# sunbeam2.net
KiCad netlist of a schematic drawn in EAGLE
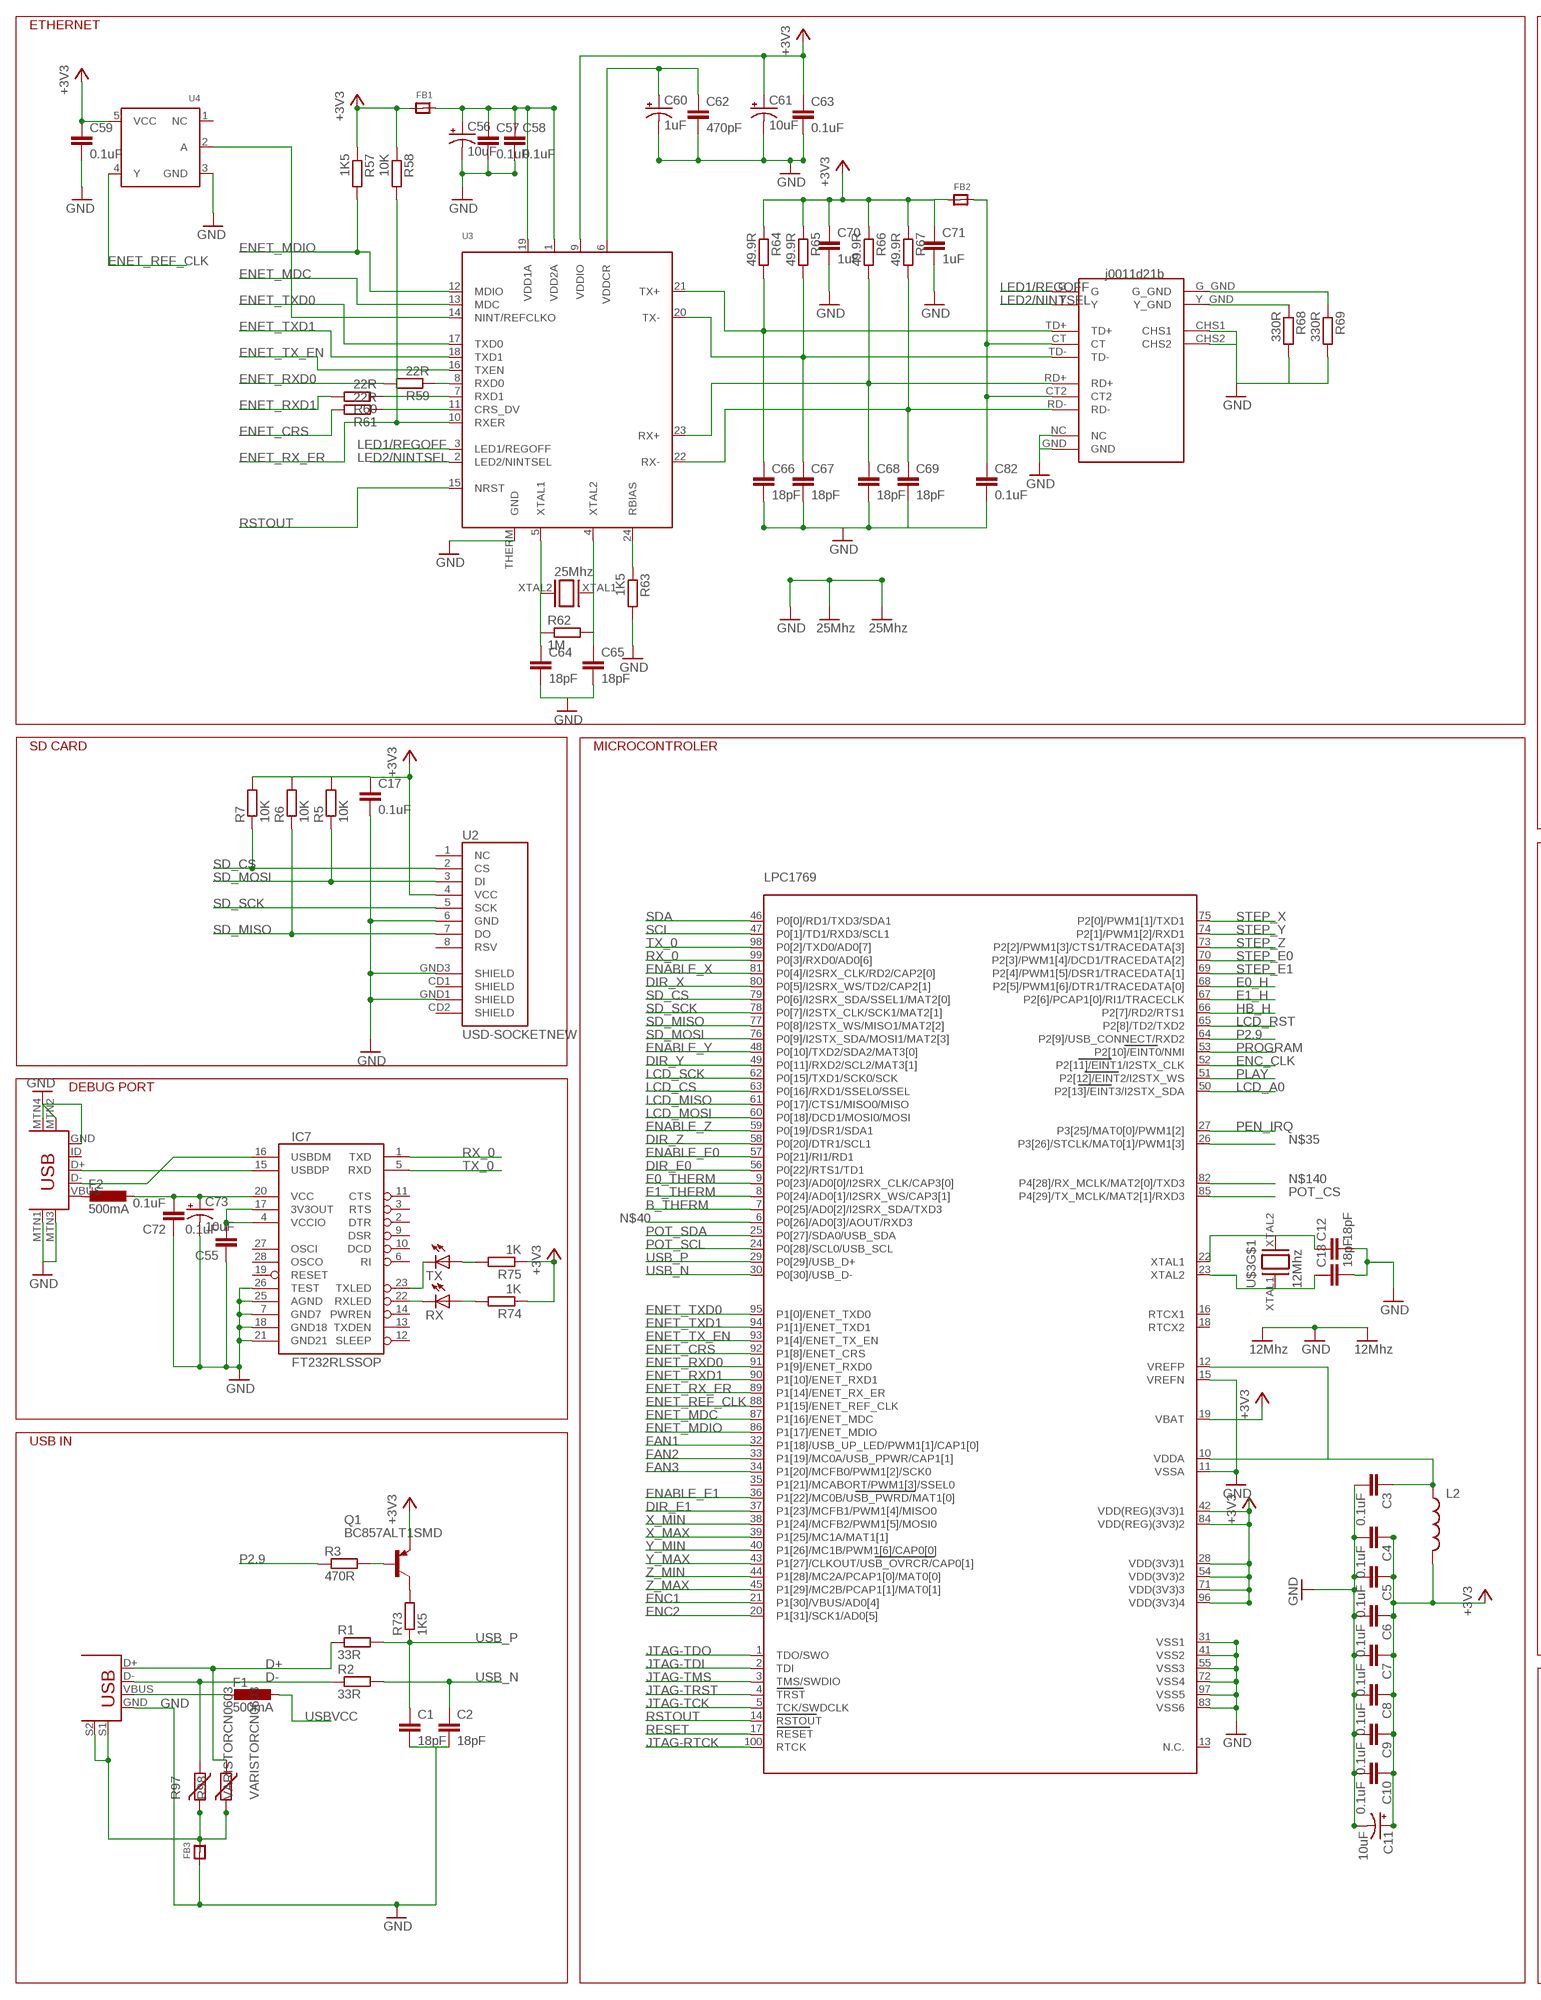
[diagram p0: schematic, sheet 1, part 1 of 2]
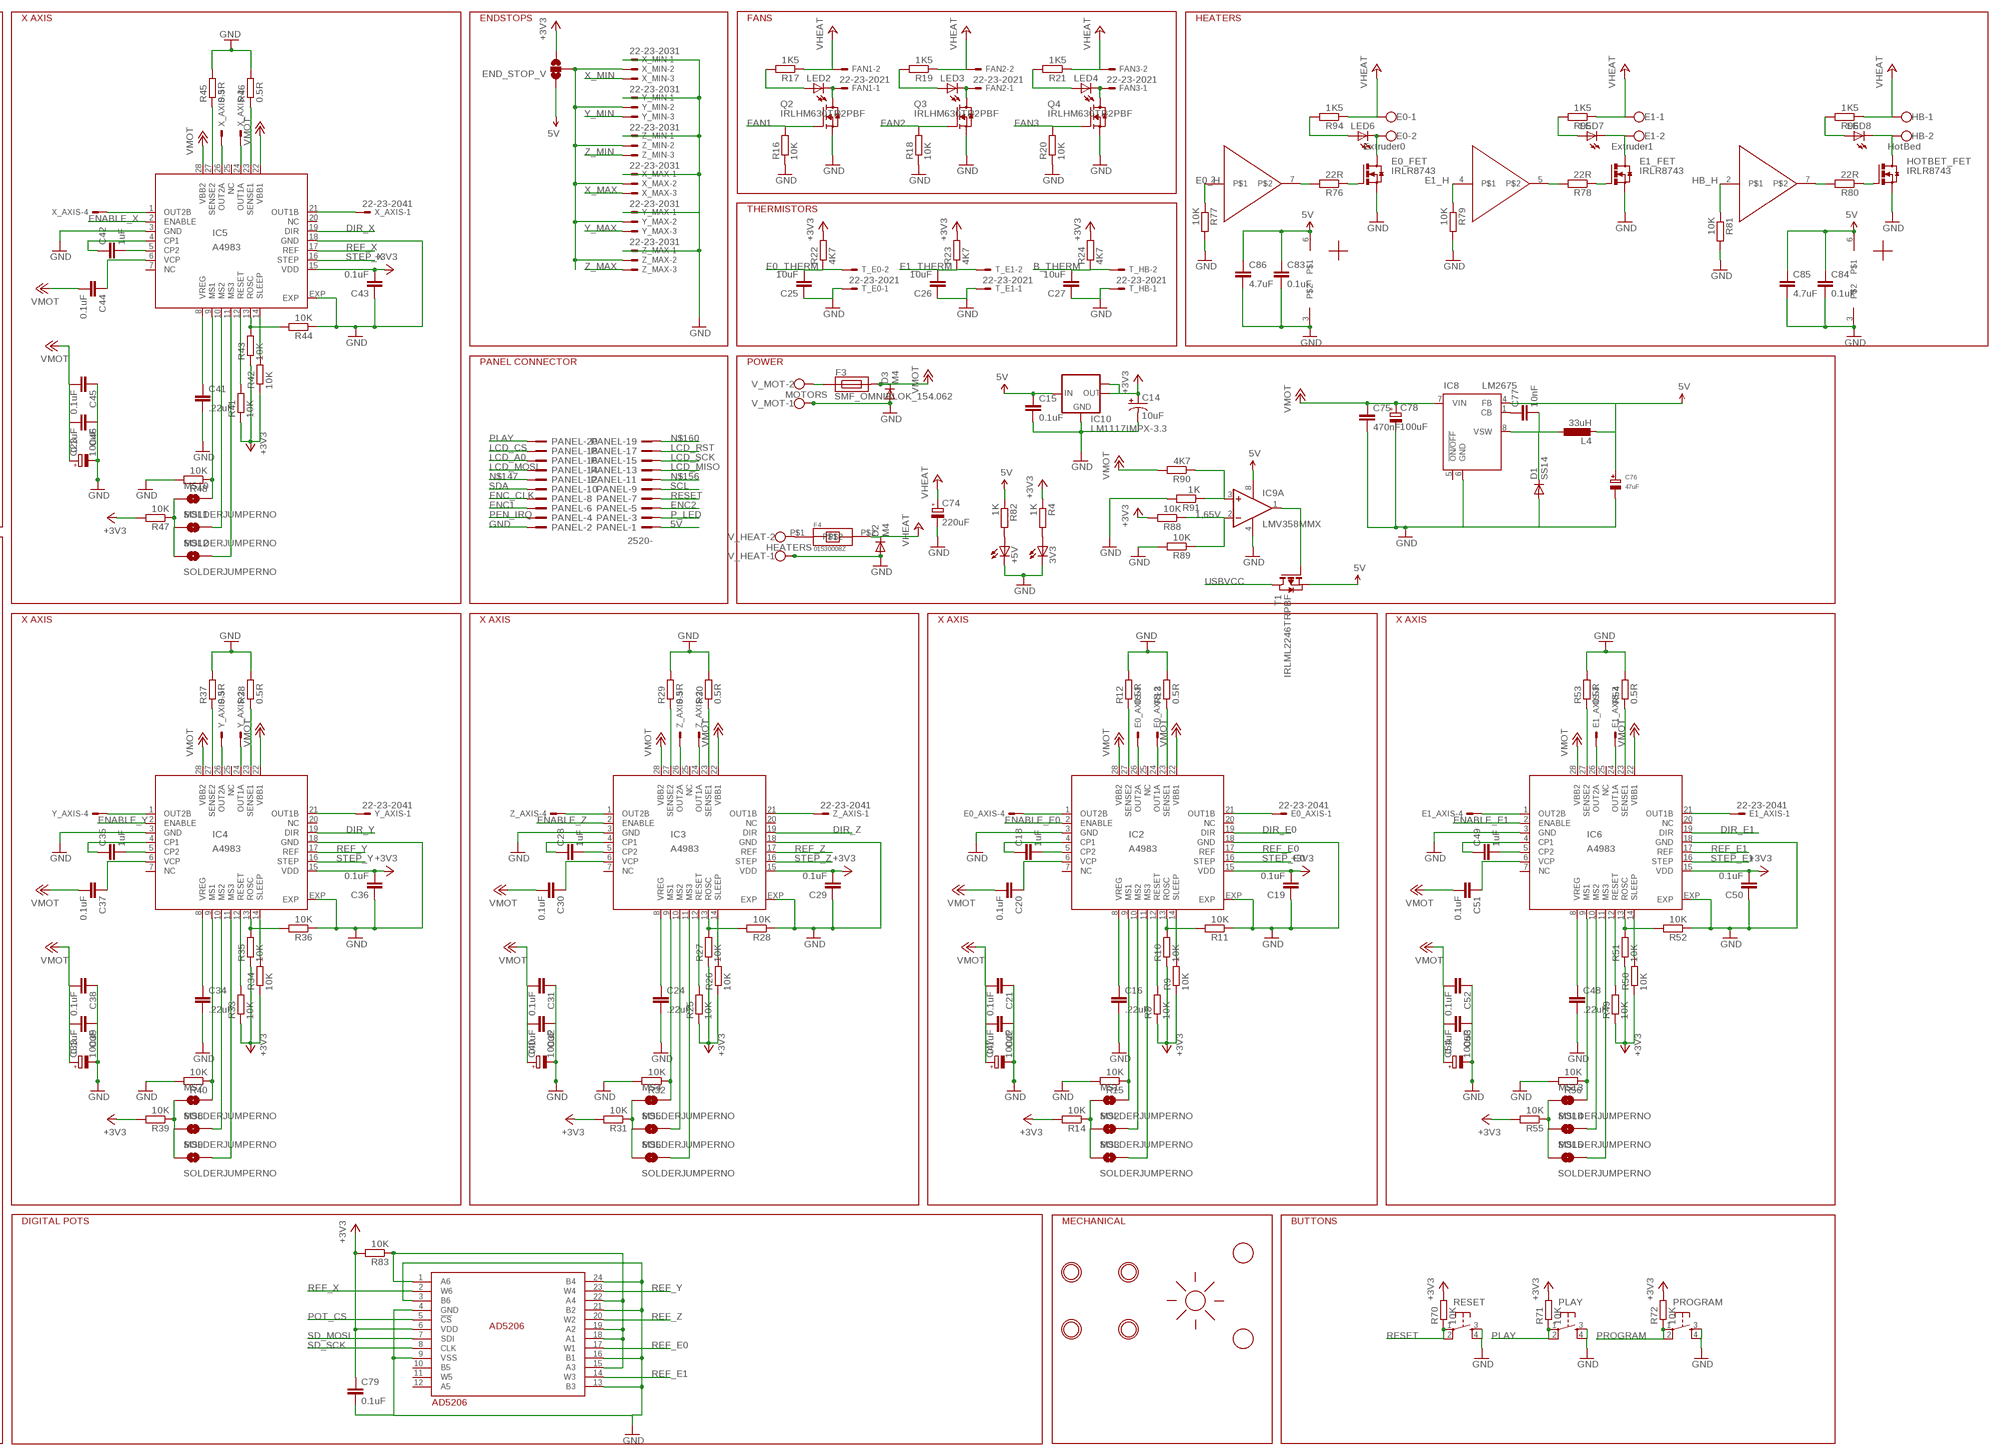
[diagram p1: schematic, sheet 1, part 2 of 2]

(export (version "E")
  (design (tool "Eeschema 10.0.6"))
  (components
    (comp (ref "+5V")
      (value "LEDCHIPLED_0805")
      (footprint "eagle-import:CHIPLED_0805")
      (libsource (lib "eagle-import") (part "LEDCHIPLED_0805"))
    )
    (comp (ref "3V3")
      (value "LEDCHIPLED_0805")
      (footprint "eagle-import:CHIPLED_0805")
      (libsource (lib "eagle-import") (part "LEDCHIPLED_0805"))
    )
    (comp (ref "AD5206")
      (value "AD5206")
      (footprint "eagle-import:TSSOP24")
      (libsource (lib "eagle-import") (part "AD5206"))
    )
    (comp (ref "C1")
      (value "18pF")
      (footprint "eagle-import:C0603")
      (libsource (lib "eagle-import") (part "C-EUC0603"))
    )
    (comp (ref "C2")
      (value "18pF")
      (footprint "eagle-import:C0603")
      (libsource (lib "eagle-import") (part "C-EUC0603"))
    )
    (comp (ref "C3")
      (value "0.1uF")
      (footprint "eagle-import:C0603")
      (libsource (lib "eagle-import") (part "C-EUC0603"))
    )
    (comp (ref "C4")
      (value "0.1uF")
      (footprint "eagle-import:C0603")
      (libsource (lib "eagle-import") (part "C-EUC0603"))
    )
    (comp (ref "C5")
      (value "0.1uF")
      (footprint "eagle-import:C0603")
      (libsource (lib "eagle-import") (part "C-EUC0603"))
    )
    (comp (ref "C6")
      (value "0.1uF")
      (footprint "eagle-import:C0603")
      (libsource (lib "eagle-import") (part "C-EUC0603"))
    )
    (comp (ref "C7")
      (value "0.1uF")
      (footprint "eagle-import:C0603")
      (libsource (lib "eagle-import") (part "C-EUC0603"))
    )
    (comp (ref "C8")
      (value "0.1uF")
      (footprint "eagle-import:C0603")
      (libsource (lib "eagle-import") (part "C-EUC0603"))
    )
    (comp (ref "C9")
      (value "0.1uF")
      (footprint "eagle-import:C0603")
      (libsource (lib "eagle-import") (part "C-EUC0603"))
    )
    (comp (ref "C10")
      (value "0.1uF")
      (footprint "eagle-import:C0603")
      (libsource (lib "eagle-import") (part "C-EUC0603"))
    )
    (comp (ref "C11")
      (value "10uF")
      (footprint "eagle-import:EIA3216")
      (libsource (lib "eagle-import") (part "CAP_POL1206"))
    )
    (comp (ref "C12")
      (value "18pF")
      (footprint "eagle-import:C0603")
      (libsource (lib "eagle-import") (part "C-EUC0603"))
    )
    (comp (ref "C13")
      (value "18pF")
      (footprint "eagle-import:C0603")
      (libsource (lib "eagle-import") (part "C-EUC0603"))
    )
    (comp (ref "C14")
      (value "10uF")
      (footprint "eagle-import:EIA3216")
      (libsource (lib "eagle-import") (part "CAP_POL1206"))
    )
    (comp (ref "C15")
      (value "0.1uF")
      (footprint "eagle-import:C0805")
      (libsource (lib "eagle-import") (part "C-EUC0805"))
    )
    (comp (ref "C16")
      (value ".22uF")
      (footprint "eagle-import:C0603")
      (libsource (lib "eagle-import") (part "C-EUC0603"))
    )
    (comp (ref "C17")
      (value "0.1uF")
      (footprint "eagle-import:C0603")
      (libsource (lib "eagle-import") (part "C-EUC0603"))
    )
    (comp (ref "C18")
      (value "1uF")
      (footprint "eagle-import:C0603")
      (libsource (lib "eagle-import") (part "C-EUC0603"))
    )
    (comp (ref "C19")
      (value "0.1uF")
      (footprint "eagle-import:C0603")
      (libsource (lib "eagle-import") (part "C-EUC0603"))
    )
    (comp (ref "C20")
      (value "0.1uF")
      (footprint "eagle-import:C0805")
      (libsource (lib "eagle-import") (part "C-EUC0805"))
    )
    (comp (ref "C21")
      (value "0.1uF")
      (footprint "eagle-import:C0805")
      (libsource (lib "eagle-import") (part "C-EUC0805"))
    )
    (comp (ref "C22")
      (value "0.1uF")
      (footprint "eagle-import:C0805")
      (libsource (lib "eagle-import") (part "C-EUC0805"))
    )
    (comp (ref "C23")
      (value "100uF")
      (footprint "eagle-import:UD-6,3X7,7_NICHICON")
      (libsource (lib "eagle-import") (part "CPOL-EUUD-6,3X7,7"))
    )
    (comp (ref "C24")
      (value ".22uF")
      (footprint "eagle-import:C0603")
      (libsource (lib "eagle-import") (part "C-EUC0603"))
    )
    (comp (ref "C25")
      (value "10uF")
      (footprint "eagle-import:C0603")
      (libsource (lib "eagle-import") (part "C-EUC0603"))
    )
    (comp (ref "C26")
      (value "10uF")
      (footprint "eagle-import:C0603")
      (libsource (lib "eagle-import") (part "C-EUC0603"))
    )
    (comp (ref "C27")
      (value "10uF")
      (footprint "eagle-import:C0603")
      (libsource (lib "eagle-import") (part "C-EUC0603"))
    )
    (comp (ref "C28")
      (value "1uF")
      (footprint "eagle-import:C0603")
      (libsource (lib "eagle-import") (part "C-EUC0603"))
    )
    (comp (ref "C29")
      (value "0.1uF")
      (footprint "eagle-import:C0603")
      (libsource (lib "eagle-import") (part "C-EUC0603"))
    )
    (comp (ref "C30")
      (value "0.1uF")
      (footprint "eagle-import:C0805")
      (libsource (lib "eagle-import") (part "C-EUC0805"))
    )
    (comp (ref "C31")
      (value "0.1uF")
      (footprint "eagle-import:C0805")
      (libsource (lib "eagle-import") (part "C-EUC0805"))
    )
    (comp (ref "C32")
      (value "0.1uF")
      (footprint "eagle-import:C0805")
      (libsource (lib "eagle-import") (part "C-EUC0805"))
    )
    (comp (ref "C33")
      (value "100uF")
      (footprint "eagle-import:UD-6,3X7,7_NICHICON")
      (libsource (lib "eagle-import") (part "CPOL-EUUD-6,3X7,7"))
    )
    (comp (ref "C34")
      (value ".22uF")
      (footprint "eagle-import:C0603")
      (libsource (lib "eagle-import") (part "C-EUC0603"))
    )
    (comp (ref "C35")
      (value "1uF")
      (footprint "eagle-import:C0603")
      (libsource (lib "eagle-import") (part "C-EUC0603"))
    )
    (comp (ref "C36")
      (value "0.1uF")
      (footprint "eagle-import:C0603")
      (libsource (lib "eagle-import") (part "C-EUC0603"))
    )
    (comp (ref "C37")
      (value "0.1uF")
      (footprint "eagle-import:C0805")
      (libsource (lib "eagle-import") (part "C-EUC0805"))
    )
    (comp (ref "C38")
      (value "0.1uF")
      (footprint "eagle-import:C0805")
      (libsource (lib "eagle-import") (part "C-EUC0805"))
    )
    (comp (ref "C39")
      (value "0.1uF")
      (footprint "eagle-import:C0805")
      (libsource (lib "eagle-import") (part "C-EUC0805"))
    )
    (comp (ref "C40")
      (value "100uF")
      (footprint "eagle-import:UD-6,3X7,7_NICHICON")
      (libsource (lib "eagle-import") (part "CPOL-EUUD-6,3X7,7"))
    )
    (comp (ref "C41")
      (value ".22uF")
      (footprint "eagle-import:C0603")
      (libsource (lib "eagle-import") (part "C-EUC0603"))
    )
    (comp (ref "C42")
      (value "1uF")
      (footprint "eagle-import:C0603")
      (libsource (lib "eagle-import") (part "C-EUC0603"))
    )
    (comp (ref "C43")
      (value "0.1uF")
      (footprint "eagle-import:C0603")
      (libsource (lib "eagle-import") (part "C-EUC0603"))
    )
    (comp (ref "C44")
      (value "0.1uF")
      (footprint "eagle-import:C0805")
      (libsource (lib "eagle-import") (part "C-EUC0805"))
    )
    (comp (ref "C45")
      (value "0.1uF")
      (footprint "eagle-import:C0805")
      (libsource (lib "eagle-import") (part "C-EUC0805"))
    )
    (comp (ref "C46")
      (value "0.1uF")
      (footprint "eagle-import:C0805")
      (libsource (lib "eagle-import") (part "C-EUC0805"))
    )
    (comp (ref "C47")
      (value "100uF")
      (footprint "eagle-import:UD-6,3X7,7_NICHICON")
      (libsource (lib "eagle-import") (part "CPOL-EUUD-6,3X7,7"))
    )
    (comp (ref "C48")
      (value ".22uF")
      (footprint "eagle-import:C0603")
      (libsource (lib "eagle-import") (part "C-EUC0603"))
    )
    (comp (ref "C49")
      (value "1uF")
      (footprint "eagle-import:C0603")
      (libsource (lib "eagle-import") (part "C-EUC0603"))
    )
    (comp (ref "C50")
      (value "0.1uF")
      (footprint "eagle-import:C0603")
      (libsource (lib "eagle-import") (part "C-EUC0603"))
    )
    (comp (ref "C51")
      (value "0.1uF")
      (footprint "eagle-import:C0805")
      (libsource (lib "eagle-import") (part "C-EUC0805"))
    )
    (comp (ref "C52")
      (value "0.1uF")
      (footprint "eagle-import:C0805")
      (libsource (lib "eagle-import") (part "C-EUC0805"))
    )
    (comp (ref "C53")
      (value "0.1uF")
      (footprint "eagle-import:C0805")
      (libsource (lib "eagle-import") (part "C-EUC0805"))
    )
    (comp (ref "C54")
      (value "100uF")
      (footprint "eagle-import:UD-6,3X7,7_NICHICON")
      (libsource (lib "eagle-import") (part "CPOL-EUUD-6,3X7,7"))
    )
    (comp (ref "C55")
      (value "0.1uF")
      (footprint "eagle-import:C0603")
      (libsource (lib "eagle-import") (part "C-EUC0603"))
    )
    (comp (ref "C56")
      (value "10uF")
      (footprint "eagle-import:EIA3216")
      (libsource (lib "eagle-import") (part "CAP_POL1206"))
    )
    (comp (ref "C57")
      (value "0.1uF")
      (footprint "eagle-import:C0603")
      (libsource (lib "eagle-import") (part "C-EUC0603"))
    )
    (comp (ref "C58")
      (value "0.1uF")
      (footprint "eagle-import:C0603")
      (libsource (lib "eagle-import") (part "C-EUC0603"))
    )
    (comp (ref "C59")
      (value "0.1uF")
      (footprint "eagle-import:C0603")
      (libsource (lib "eagle-import") (part "C-EUC0603"))
    )
    (comp (ref "C60")
      (value "1uF")
      (footprint "eagle-import:EIA3216")
      (libsource (lib "eagle-import") (part "CAP_POL1206"))
    )
    (comp (ref "C61")
      (value "10uF")
      (footprint "eagle-import:EIA3216")
      (libsource (lib "eagle-import") (part "CAP_POL1206"))
    )
    (comp (ref "C62")
      (value "470pF")
      (footprint "eagle-import:C0603")
      (libsource (lib "eagle-import") (part "C-EUC0603"))
    )
    (comp (ref "C63")
      (value "0.1uF")
      (footprint "eagle-import:C0603")
      (libsource (lib "eagle-import") (part "C-EUC0603"))
    )
    (comp (ref "C64")
      (value "18pF")
      (footprint "eagle-import:C0603")
      (libsource (lib "eagle-import") (part "C-EUC0603"))
    )
    (comp (ref "C65")
      (value "18pF")
      (footprint "eagle-import:C0603")
      (libsource (lib "eagle-import") (part "C-EUC0603"))
    )
    (comp (ref "C66")
      (value "18pF")
      (footprint "eagle-import:C0603")
      (libsource (lib "eagle-import") (part "C-EUC0603"))
    )
    (comp (ref "C67")
      (value "18pF")
      (footprint "eagle-import:C0603")
      (libsource (lib "eagle-import") (part "C-EUC0603"))
    )
    (comp (ref "C68")
      (value "18pF")
      (footprint "eagle-import:C0603")
      (libsource (lib "eagle-import") (part "C-EUC0603"))
    )
    (comp (ref "C69")
      (value "18pF")
      (footprint "eagle-import:C0603")
      (libsource (lib "eagle-import") (part "C-EUC0603"))
    )
    (comp (ref "C70")
      (value "1uF")
      (footprint "eagle-import:C0603")
      (libsource (lib "eagle-import") (part "C-EUC0603"))
    )
    (comp (ref "C71")
      (value "1uF")
      (footprint "eagle-import:C0603")
      (libsource (lib "eagle-import") (part "C-EUC0603"))
    )
    (comp (ref "C72")
      (value "0.1uF")
      (footprint "eagle-import:C0603")
      (libsource (lib "eagle-import") (part "C-EUC0603"))
    )
    (comp (ref "C73")
      (value "10uF")
      (footprint "eagle-import:EIA3216")
      (libsource (lib "eagle-import") (part "CAP_POL1206"))
    )
    (comp (ref "C74")
      (value "220uF")
      (footprint "eagle-import:UD-8X10_NICHICON")
      (libsource (lib "eagle-import") (part "CPOL-EUUD-8X10"))
    )
    (comp (ref "C75")
      (value "470nF")
      (footprint "eagle-import:C0805")
      (libsource (lib "eagle-import") (part "C-EUC0805"))
    )
    (comp (ref "C76")
      (value "47uF")
      (footprint "eagle-import:EIA7343-31_D-R")
      (libsource (lib "eagle-import") (part "CAP_TANTALUMD/7343_REFLOW"))
    )
    (comp (ref "C77")
      (value "10nF")
      (footprint "eagle-import:C0805")
      (libsource (lib "eagle-import") (part "C-EUC0805"))
    )
    (comp (ref "C78")
      (value "100uF")
      (footprint "eagle-import:UD-8X10_NICHICON")
      (libsource (lib "eagle-import") (part "CPOL-EUUD-8X10"))
    )
    (comp (ref "C79")
      (value "0.1uF")
      (footprint "eagle-import:C0603")
      (libsource (lib "eagle-import") (part "C-EUC0603"))
    )
    (comp (ref "C82")
      (value "0.1uF")
      (footprint "eagle-import:C0603")
      (libsource (lib "eagle-import") (part "C-EUC0603"))
    )
    (comp (ref "C83")
      (value "0.1uF")
      (footprint "eagle-import:C0603")
      (libsource (lib "eagle-import") (part "C-EUC0603"))
    )
    (comp (ref "C84")
      (value "0.1uF")
      (footprint "eagle-import:C0603")
      (libsource (lib "eagle-import") (part "C-EUC0603"))
    )
    (comp (ref "C85")
      (value "4.7uF")
      (footprint "eagle-import:C0603")
      (libsource (lib "eagle-import") (part "C-EUC0603"))
    )
    (comp (ref "C86")
      (value "4.7uF")
      (footprint "eagle-import:C0603")
      (libsource (lib "eagle-import") (part "C-EUC0603"))
    )
    (comp (ref "D1")
      (value "SS14")
      (footprint "eagle-import:DO214AC")
      (libsource (lib "eagle-import") (part "DIODE-DO214AC"))
    )
    (comp (ref "D2")
      (value "M4")
      (footprint "eagle-import:DO214AC")
      (libsource (lib "eagle-import") (part "DIODE-DO214AC"))
    )
    (comp (ref "D3")
      (value "M4")
      (footprint "eagle-import:DO214AC")
      (libsource (lib "eagle-import") (part "DIODE-DO214AC"))
    )
    (comp (ref "E0")
      (value "Extruder0")
      (footprint "eagle-import:W237-102")
      (fields
        (field (name "MPN") "237-102")
        (field (name "MPN_1") "237-102")
        (field (name "OC_FARNELL") "unknown")
        (field (name "OC_NEWARK") "70K9898")
      )
      (libsource (lib "eagle-import") (part "W237-102"))
    )
    (comp (ref "E0_AXIS")
      (value "22-23-2041")
      (footprint "eagle-import:22-23-2041")
      (fields (field (name "MF") "MOLEX"))
      (libsource (lib "eagle-import") (part "22-23-2041"))
    )
    (comp (ref "E0_FET")
      (value "IRLR8743")
      (footprint "eagle-import:D-PAK_TO252AA")
      (libsource (lib "eagle-import") (part "IRLR8743"))
    )
    (comp (ref "E1")
      (value "Extruder1")
      (footprint "eagle-import:W237-102")
      (fields
        (field (name "MPN") "237-102")
        (field (name "MPN_1") "237-102")
        (field (name "OC_FARNELL") "unknown")
        (field (name "OC_NEWARK") "70K9898")
      )
      (libsource (lib "eagle-import") (part "W237-102"))
    )
    (comp (ref "E1_AXIS")
      (value "22-23-2041")
      (footprint "eagle-import:22-23-2041")
      (fields (field (name "MF") "MOLEX"))
      (libsource (lib "eagle-import") (part "22-23-2041"))
    )
    (comp (ref "E1_FET")
      (value "IRLR8743")
      (footprint "eagle-import:D-PAK_TO252AA")
      (libsource (lib "eagle-import") (part "IRLR8743"))
    )
    (comp (ref "END_STOP_V")
      (value "SOLDERJUMPER_2WAYS")
      (footprint "eagle-import:SJ_3")
      (libsource (lib "eagle-import") (part "SOLDERJUMPER_2WAYS"))
    )
    (comp (ref "F1")
      (value "500mA")
      (footprint "eagle-import:L1812")
      (libsource (lib "eagle-import") (part "L-EUL1812"))
    )
    (comp (ref "F2")
      (value "500mA")
      (footprint "eagle-import:L1812")
      (libsource (lib "eagle-import") (part "L-EUL1812"))
    )
    (comp (ref "F3")
      (value "SMF_OMNIBLOK_154.062")
      (footprint "eagle-import:NANO2_SMF_FUSEBLOCK")
      (libsource (lib "eagle-import") (part "SMF_OMNIBLOK_154.062"))
    )
    (comp (ref "F4")
      (value "01530008Z")
      (footprint "eagle-import:01530008Z")
      (libsource (lib "eagle-import") (part "01530008Z"))
    )
    (comp (ref "FAN1")
      (value "22-23-2021")
      (footprint "eagle-import:22-23-2021")
      (fields (field (name "MF") "MOLEX"))
      (libsource (lib "eagle-import") (part "22-23-2021"))
    )
    (comp (ref "FAN2")
      (value "22-23-2021")
      (footprint "eagle-import:22-23-2021")
      (fields (field (name "MF") "MOLEX"))
      (libsource (lib "eagle-import") (part "22-23-2021"))
    )
    (comp (ref "FAN3")
      (value "22-23-2021")
      (footprint "eagle-import:22-23-2021")
      (fields (field (name "MF") "MOLEX"))
      (libsource (lib "eagle-import") (part "22-23-2021"))
    )
    (comp (ref "FB1")
      (value "FERRITE_0603")
      (footprint "eagle-import:_0603")
      (libsource (lib "eagle-import") (part "FERRITE_0603"))
    )
    (comp (ref "FB2")
      (value "FERRITE_0603")
      (footprint "eagle-import:_0603")
      (libsource (lib "eagle-import") (part "FERRITE_0603"))
    )
    (comp (ref "FB3")
      (value "FERRITE_0603")
      (footprint "eagle-import:_0603")
      (libsource (lib "eagle-import") (part "FERRITE_0603"))
    )
    (comp (ref "FET_DRV1")
      (value "TC4427")
      (footprint "eagle-import:SOIC8")
      (libsource (lib "eagle-import") (part "TC4427"))
    )
    (comp (ref "FET_DRV2")
      (value "TC4427")
      (footprint "eagle-import:SOIC8")
      (libsource (lib "eagle-import") (part "TC4427"))
    )
    (comp (ref "GND")
      (value "MOUNTINGHOLE3.0THIN")
      (footprint "eagle-import:MOUNTINGHOLE_3.0_PLATEDTHIN")
      (libsource (lib "eagle-import") (part "MOUNTINGHOLE3.0THIN"))
    )
    (comp (ref "HB")
      (value "HotBed")
      (footprint "eagle-import:W237-102")
      (fields
        (field (name "MPN") "237-102")
        (field (name "MPN_1") "237-102")
        (field (name "OC_FARNELL") "unknown")
        (field (name "OC_NEWARK") "70K9898")
      )
      (libsource (lib "eagle-import") (part "W237-102"))
    )
    (comp (ref "HOTBET_FET")
      (value "IRLR8743")
      (footprint "eagle-import:D-PAK_TO252AA")
      (libsource (lib "eagle-import") (part "IRLR8743"))
    )
    (comp (ref "IC2")
      (value "A4983")
      (footprint "eagle-import:QFN28ET")
      (fields (field (name "MPN") "A4983SETTR-T"))
      (libsource (lib "eagle-import") (part "A4983"))
    )
    (comp (ref "IC3")
      (value "A4983")
      (footprint "eagle-import:QFN28ET")
      (fields (field (name "MPN") "A4983SETTR-T"))
      (libsource (lib "eagle-import") (part "A4983"))
    )
    (comp (ref "IC4")
      (value "A4983")
      (footprint "eagle-import:QFN28ET")
      (fields (field (name "MPN") "A4983SETTR-T"))
      (libsource (lib "eagle-import") (part "A4983"))
    )
    (comp (ref "IC5")
      (value "A4983")
      (footprint "eagle-import:QFN28ET")
      (fields (field (name "MPN") "A4983SETTR-T"))
      (libsource (lib "eagle-import") (part "A4983"))
    )
    (comp (ref "IC6")
      (value "A4983")
      (footprint "eagle-import:QFN28ET")
      (fields (field (name "MPN") "A4983SETTR-T"))
      (libsource (lib "eagle-import") (part "A4983"))
    )
    (comp (ref "IC7")
      (value "FT232RLSSOP")
      (footprint "eagle-import:SSOP28DB")
      (libsource (lib "eagle-import") (part "FT232RLSSOP"))
    )
    (comp (ref "IC8")
      (value "LM2675")
      (footprint "eagle-import:SO08")
      (libsource (lib "eagle-import") (part "LM2675"))
    )
    (comp (ref "IC9")
      (value "LMV358MMX")
      (footprint "eagle-import:MSOP08")
      (libsource (lib "eagle-import") (part "LMV358?MMX"))
    )
    (comp (ref "IC10")
      (value "LM1117IMPX-3.3")
      (footprint "eagle-import:SOT223")
      (libsource (lib "eagle-import") (part "LM1117IMPX-3.3"))
    )
    (comp (ref "L2")
      (value "INDUCTOR0603")
      (footprint "eagle-import:0603")
      (libsource (lib "eagle-import") (part "INDUCTOR0603"))
    )
    (comp (ref "L4")
      (value "33uH")
      (footprint "eagle-import:PIS2816")
      (libsource (lib "eagle-import") (part "L-EUPIS2816"))
    )
    (comp (ref "LED2")
      (value "LEDCHIPLED_0805")
      (footprint "eagle-import:CHIPLED_0805")
      (libsource (lib "eagle-import") (part "LEDCHIPLED_0805"))
    )
    (comp (ref "LED3")
      (value "LEDCHIPLED_0805")
      (footprint "eagle-import:CHIPLED_0805")
      (libsource (lib "eagle-import") (part "LEDCHIPLED_0805"))
    )
    (comp (ref "LED4")
      (value "LEDCHIPLED_0805")
      (footprint "eagle-import:CHIPLED_0805")
      (libsource (lib "eagle-import") (part "LEDCHIPLED_0805"))
    )
    (comp (ref "LED6")
      (value "LEDCHIPLED_0805")
      (footprint "eagle-import:CHIPLED_0805")
      (libsource (lib "eagle-import") (part "LEDCHIPLED_0805"))
    )
    (comp (ref "LED7")
      (value "LEDCHIPLED_0805")
      (footprint "eagle-import:CHIPLED_0805")
      (libsource (lib "eagle-import") (part "LEDCHIPLED_0805"))
    )
    (comp (ref "LED8")
      (value "LEDCHIPLED_0805")
      (footprint "eagle-import:CHIPLED_0805")
      (libsource (lib "eagle-import") (part "LEDCHIPLED_0805"))
    )
    (comp (ref "LPC1769")
      (value "LPC1768")
      (footprint "eagle-import:LQFP100")
      (libsource (lib "eagle-import") (part "LPC1768"))
    )
    (comp (ref "MS1")
      (value "SOLDERJUMPERNO")
      (footprint "eagle-import:SJ_2S-NO")
      (libsource (lib "eagle-import") (part "SOLDERJUMPERNO"))
    )
    (comp (ref "MS2")
      (value "SOLDERJUMPERNO")
      (footprint "eagle-import:SJ_2S-NO")
      (libsource (lib "eagle-import") (part "SOLDERJUMPERNO"))
    )
    (comp (ref "MS3")
      (value "SOLDERJUMPERNO")
      (footprint "eagle-import:SJ_2S-NO")
      (libsource (lib "eagle-import") (part "SOLDERJUMPERNO"))
    )
    (comp (ref "MS4")
      (value "SOLDERJUMPERNO")
      (footprint "eagle-import:SJ_2S-NO")
      (libsource (lib "eagle-import") (part "SOLDERJUMPERNO"))
    )
    (comp (ref "MS5")
      (value "SOLDERJUMPERNO")
      (footprint "eagle-import:SJ_2S-NO")
      (libsource (lib "eagle-import") (part "SOLDERJUMPERNO"))
    )
    (comp (ref "MS6")
      (value "SOLDERJUMPERNO")
      (footprint "eagle-import:SJ_2S-NO")
      (libsource (lib "eagle-import") (part "SOLDERJUMPERNO"))
    )
    (comp (ref "MS7")
      (value "SOLDERJUMPERNO")
      (footprint "eagle-import:SJ_2S-NO")
      (libsource (lib "eagle-import") (part "SOLDERJUMPERNO"))
    )
    (comp (ref "MS8")
      (value "SOLDERJUMPERNO")
      (footprint "eagle-import:SJ_2S-NO")
      (libsource (lib "eagle-import") (part "SOLDERJUMPERNO"))
    )
    (comp (ref "MS9")
      (value "SOLDERJUMPERNO")
      (footprint "eagle-import:SJ_2S-NO")
      (libsource (lib "eagle-import") (part "SOLDERJUMPERNO"))
    )
    (comp (ref "MS10")
      (value "SOLDERJUMPERNO")
      (footprint "eagle-import:SJ_2S-NO")
      (libsource (lib "eagle-import") (part "SOLDERJUMPERNO"))
    )
    (comp (ref "MS11")
      (value "SOLDERJUMPERNO")
      (footprint "eagle-import:SJ_2S-NO")
      (libsource (lib "eagle-import") (part "SOLDERJUMPERNO"))
    )
    (comp (ref "MS12")
      (value "SOLDERJUMPERNO")
      (footprint "eagle-import:SJ_2S-NO")
      (libsource (lib "eagle-import") (part "SOLDERJUMPERNO"))
    )
    (comp (ref "MS13")
      (value "SOLDERJUMPERNO")
      (footprint "eagle-import:SJ_2S-NO")
      (libsource (lib "eagle-import") (part "SOLDERJUMPERNO"))
    )
    (comp (ref "MS14")
      (value "SOLDERJUMPERNO")
      (footprint "eagle-import:SJ_2S-NO")
      (libsource (lib "eagle-import") (part "SOLDERJUMPERNO"))
    )
    (comp (ref "MS15")
      (value "SOLDERJUMPERNO")
      (footprint "eagle-import:SJ_2S-NO")
      (libsource (lib "eagle-import") (part "SOLDERJUMPERNO"))
    )
    (comp (ref "PANEL")
      (value "2520-")
      (footprint "eagle-import:PAK100_2500-20")
      (libsource (lib "eagle-import") (part "2520-"))
    )
    (comp (ref "PLAY")
      (value "TAC_SWITCHSMD")
      (footprint "eagle-import:TACTILE_SWITCH_SMD")
      (libsource (lib "eagle-import") (part "TAC_SWITCHSMD"))
    )
    (comp (ref "PROGRAM")
      (value "TAC_SWITCHSMD")
      (footprint "eagle-import:TACTILE_SWITCH_SMD")
      (libsource (lib "eagle-import") (part "TAC_SWITCHSMD"))
    )
    (comp (ref "Q1")
      (value "BC857ALT1SMD")
      (footprint "eagle-import:SOT23-BEC")
      (libsource (lib "eagle-import") (part "BC857SMDALT1"))
    )
    (comp (ref "Q2")
      (value "IRLHM630TR2PBF")
      (footprint "eagle-import:PQFN33")
      (libsource (lib "eagle-import") (part "IRLHM630PBF"))
    )
    (comp (ref "Q3")
      (value "IRLHM630TR2PBF")
      (footprint "eagle-import:PQFN33")
      (libsource (lib "eagle-import") (part "IRLHM630PBF"))
    )
    (comp (ref "Q4")
      (value "IRLHM630TR2PBF")
      (footprint "eagle-import:PQFN33")
      (libsource (lib "eagle-import") (part "IRLHM630PBF"))
    )
    (comp (ref "R1")
      (value "33R")
      (footprint "eagle-import:R0603")
      (libsource (lib "eagle-import") (part "R-EU_R0603"))
    )
    (comp (ref "R2")
      (value "33R")
      (footprint "eagle-import:R0603")
      (libsource (lib "eagle-import") (part "R-EU_R0603"))
    )
    (comp (ref "R3")
      (value "470R")
      (footprint "eagle-import:R0603")
      (libsource (lib "eagle-import") (part "R-EU_R0603"))
    )
    (comp (ref "R4")
      (value "1K")
      (footprint "eagle-import:R0603")
      (libsource (lib "eagle-import") (part "R-EU_R0603"))
    )
    (comp (ref "R5")
      (value "10K")
      (footprint "eagle-import:R0603")
      (libsource (lib "eagle-import") (part "R-EU_R0603"))
    )
    (comp (ref "R6")
      (value "10K")
      (footprint "eagle-import:R0603")
      (libsource (lib "eagle-import") (part "R-EU_R0603"))
    )
    (comp (ref "R7")
      (value "10K")
      (footprint "eagle-import:R0603")
      (libsource (lib "eagle-import") (part "R-EU_R0603"))
    )
    (comp (ref "R8")
      (value "10K")
      (footprint "eagle-import:R0603")
      (libsource (lib "eagle-import") (part "R-EU_R0603"))
    )
    (comp (ref "R9")
      (value "10K")
      (footprint "eagle-import:R0603")
      (libsource (lib "eagle-import") (part "R-EU_R0603"))
    )
    (comp (ref "R10")
      (value "10K")
      (footprint "eagle-import:R0603")
      (libsource (lib "eagle-import") (part "R-EU_R0603"))
    )
    (comp (ref "R11")
      (value "10K")
      (footprint "eagle-import:R0603")
      (libsource (lib "eagle-import") (part "R-EU_R0603"))
    )
    (comp (ref "R12")
      (value "0.5R")
      (footprint "eagle-import:R2512")
      (libsource (lib "eagle-import") (part "R-EU_R2512"))
    )
    (comp (ref "R13")
      (value "0.5R")
      (footprint "eagle-import:R2512")
      (libsource (lib "eagle-import") (part "R-EU_R2512"))
    )
    (comp (ref "R14")
      (value "10K")
      (footprint "eagle-import:R0603")
      (libsource (lib "eagle-import") (part "R-EU_R0603"))
    )
    (comp (ref "R15")
      (value "10K")
      (footprint "eagle-import:R0603")
      (libsource (lib "eagle-import") (part "R-EU_R0603"))
    )
    (comp (ref "R16")
      (value "10K")
      (footprint "eagle-import:R0603")
      (libsource (lib "eagle-import") (part "R-EU_R0603"))
    )
    (comp (ref "R17")
      (value "1K5")
      (footprint "eagle-import:R0603")
      (libsource (lib "eagle-import") (part "R-EU_R0603"))
    )
    (comp (ref "R18")
      (value "10K")
      (footprint "eagle-import:R0603")
      (libsource (lib "eagle-import") (part "R-EU_R0603"))
    )
    (comp (ref "R19")
      (value "1K5")
      (footprint "eagle-import:R0603")
      (libsource (lib "eagle-import") (part "R-EU_R0603"))
    )
    (comp (ref "R20")
      (value "10K")
      (footprint "eagle-import:R0603")
      (libsource (lib "eagle-import") (part "R-EU_R0603"))
    )
    (comp (ref "R21")
      (value "1K5")
      (footprint "eagle-import:R0603")
      (libsource (lib "eagle-import") (part "R-EU_R0603"))
    )
    (comp (ref "R22")
      (value "4K7")
      (footprint "eagle-import:R0603")
      (libsource (lib "eagle-import") (part "R-EU_R0603"))
    )
    (comp (ref "R23")
      (value "4K7")
      (footprint "eagle-import:R0603")
      (libsource (lib "eagle-import") (part "R-EU_R0603"))
    )
    (comp (ref "R24")
      (value "4K7")
      (footprint "eagle-import:R0603")
      (libsource (lib "eagle-import") (part "R-EU_R0603"))
    )
    (comp (ref "R25")
      (value "10K")
      (footprint "eagle-import:R0603")
      (libsource (lib "eagle-import") (part "R-EU_R0603"))
    )
    (comp (ref "R26")
      (value "10K")
      (footprint "eagle-import:R0603")
      (libsource (lib "eagle-import") (part "R-EU_R0603"))
    )
    (comp (ref "R27")
      (value "10K")
      (footprint "eagle-import:R0603")
      (libsource (lib "eagle-import") (part "R-EU_R0603"))
    )
    (comp (ref "R28")
      (value "10K")
      (footprint "eagle-import:R0603")
      (libsource (lib "eagle-import") (part "R-EU_R0603"))
    )
    (comp (ref "R29")
      (value "0.5R")
      (footprint "eagle-import:R2512")
      (libsource (lib "eagle-import") (part "R-EU_R2512"))
    )
    (comp (ref "R30")
      (value "0.5R")
      (footprint "eagle-import:R2512")
      (libsource (lib "eagle-import") (part "R-EU_R2512"))
    )
    (comp (ref "R31")
      (value "10K")
      (footprint "eagle-import:R0603")
      (libsource (lib "eagle-import") (part "R-EU_R0603"))
    )
    (comp (ref "R32")
      (value "10K")
      (footprint "eagle-import:R0603")
      (libsource (lib "eagle-import") (part "R-EU_R0603"))
    )
    (comp (ref "R33")
      (value "10K")
      (footprint "eagle-import:R0603")
      (libsource (lib "eagle-import") (part "R-EU_R0603"))
    )
    (comp (ref "R34")
      (value "10K")
      (footprint "eagle-import:R0603")
      (libsource (lib "eagle-import") (part "R-EU_R0603"))
    )
    (comp (ref "R35")
      (value "10K")
      (footprint "eagle-import:R0603")
      (libsource (lib "eagle-import") (part "R-EU_R0603"))
    )
    (comp (ref "R36")
      (value "10K")
      (footprint "eagle-import:R0603")
      (libsource (lib "eagle-import") (part "R-EU_R0603"))
    )
    (comp (ref "R37")
      (value "0.5R")
      (footprint "eagle-import:R2512")
      (libsource (lib "eagle-import") (part "R-EU_R2512"))
    )
    (comp (ref "R38")
      (value "0.5R")
      (footprint "eagle-import:R2512")
      (libsource (lib "eagle-import") (part "R-EU_R2512"))
    )
    (comp (ref "R39")
      (value "10K")
      (footprint "eagle-import:R0603")
      (libsource (lib "eagle-import") (part "R-EU_R0603"))
    )
    (comp (ref "R40")
      (value "10K")
      (footprint "eagle-import:R0603")
      (libsource (lib "eagle-import") (part "R-EU_R0603"))
    )
    (comp (ref "R41")
      (value "10K")
      (footprint "eagle-import:R0603")
      (libsource (lib "eagle-import") (part "R-EU_R0603"))
    )
    (comp (ref "R42")
      (value "10K")
      (footprint "eagle-import:R0603")
      (libsource (lib "eagle-import") (part "R-EU_R0603"))
    )
    (comp (ref "R43")
      (value "10K")
      (footprint "eagle-import:R0603")
      (libsource (lib "eagle-import") (part "R-EU_R0603"))
    )
    (comp (ref "R44")
      (value "10K")
      (footprint "eagle-import:R0603")
      (libsource (lib "eagle-import") (part "R-EU_R0603"))
    )
    (comp (ref "R45")
      (value "0.5R")
      (footprint "eagle-import:R2512")
      (libsource (lib "eagle-import") (part "R-EU_R2512"))
    )
    (comp (ref "R46")
      (value "0.5R")
      (footprint "eagle-import:R2512")
      (libsource (lib "eagle-import") (part "R-EU_R2512"))
    )
    (comp (ref "R47")
      (value "10K")
      (footprint "eagle-import:R0603")
      (libsource (lib "eagle-import") (part "R-EU_R0603"))
    )
    (comp (ref "R48")
      (value "10K")
      (footprint "eagle-import:R0603")
      (libsource (lib "eagle-import") (part "R-EU_R0603"))
    )
    (comp (ref "R49")
      (value "10K")
      (footprint "eagle-import:R0603")
      (libsource (lib "eagle-import") (part "R-EU_R0603"))
    )
    (comp (ref "R50")
      (value "10K")
      (footprint "eagle-import:R0603")
      (libsource (lib "eagle-import") (part "R-EU_R0603"))
    )
    (comp (ref "R51")
      (value "10K")
      (footprint "eagle-import:R0603")
      (libsource (lib "eagle-import") (part "R-EU_R0603"))
    )
    (comp (ref "R52")
      (value "10K")
      (footprint "eagle-import:R0603")
      (libsource (lib "eagle-import") (part "R-EU_R0603"))
    )
    (comp (ref "R53")
      (value "0.5R")
      (footprint "eagle-import:R2512")
      (libsource (lib "eagle-import") (part "R-EU_R2512"))
    )
    (comp (ref "R54")
      (value "0.5R")
      (footprint "eagle-import:R2512")
      (libsource (lib "eagle-import") (part "R-EU_R2512"))
    )
    (comp (ref "R55")
      (value "10K")
      (footprint "eagle-import:R0603")
      (libsource (lib "eagle-import") (part "R-EU_R0603"))
    )
    (comp (ref "R56")
      (value "10K")
      (footprint "eagle-import:R0603")
      (libsource (lib "eagle-import") (part "R-EU_R0603"))
    )
    (comp (ref "R57")
      (value "1K5")
      (footprint "eagle-import:R0603")
      (libsource (lib "eagle-import") (part "R-EU_R0603"))
    )
    (comp (ref "R58")
      (value "10K")
      (footprint "eagle-import:R0603")
      (libsource (lib "eagle-import") (part "R-EU_R0603"))
    )
    (comp (ref "R59")
      (value "22R")
      (footprint "eagle-import:R0603")
      (libsource (lib "eagle-import") (part "R-EU_R0603"))
    )
    (comp (ref "R60")
      (value "22R")
      (footprint "eagle-import:R0603")
      (libsource (lib "eagle-import") (part "R-EU_R0603"))
    )
    (comp (ref "R61")
      (value "22R")
      (footprint "eagle-import:R0603")
      (libsource (lib "eagle-import") (part "R-EU_R0603"))
    )
    (comp (ref "R62")
      (value "1M")
      (footprint "eagle-import:R0603")
      (libsource (lib "eagle-import") (part "R-EU_R0603"))
    )
    (comp (ref "R63")
      (value "1K5")
      (footprint "eagle-import:R0603")
      (libsource (lib "eagle-import") (part "R-EU_R0603"))
    )
    (comp (ref "R64")
      (value "49.9R")
      (footprint "eagle-import:R0603")
      (libsource (lib "eagle-import") (part "R-EU_R0603"))
    )
    (comp (ref "R65")
      (value "49.9R")
      (footprint "eagle-import:R0603")
      (libsource (lib "eagle-import") (part "R-EU_R0603"))
    )
    (comp (ref "R66")
      (value "49.9R")
      (footprint "eagle-import:R0603")
      (libsource (lib "eagle-import") (part "R-EU_R0603"))
    )
    (comp (ref "R67")
      (value "49.9R")
      (footprint "eagle-import:R0603")
      (libsource (lib "eagle-import") (part "R-EU_R0603"))
    )
    (comp (ref "R68")
      (value "330R")
      (footprint "eagle-import:R0603")
      (libsource (lib "eagle-import") (part "R-EU_R0603"))
    )
    (comp (ref "R69")
      (value "330R")
      (footprint "eagle-import:R0603")
      (libsource (lib "eagle-import") (part "R-EU_R0603"))
    )
    (comp (ref "R70")
      (value "10K")
      (footprint "eagle-import:R0603")
      (libsource (lib "eagle-import") (part "R-EU_R0603"))
    )
    (comp (ref "R71")
      (value "10K")
      (footprint "eagle-import:R0603")
      (libsource (lib "eagle-import") (part "R-EU_R0603"))
    )
    (comp (ref "R72")
      (value "10K")
      (footprint "eagle-import:R0603")
      (libsource (lib "eagle-import") (part "R-EU_R0603"))
    )
    (comp (ref "R73")
      (value "1K5")
      (footprint "eagle-import:R0603")
      (libsource (lib "eagle-import") (part "R-EU_R0603"))
    )
    (comp (ref "R74")
      (value "1K")
      (footprint "eagle-import:R0603")
      (libsource (lib "eagle-import") (part "R-EU_R0603"))
    )
    (comp (ref "R75")
      (value "1K")
      (footprint "eagle-import:R0603")
      (libsource (lib "eagle-import") (part "R-EU_R0603"))
    )
    (comp (ref "R76")
      (value "22R")
      (footprint "eagle-import:R0603")
      (libsource (lib "eagle-import") (part "R-EU_R0603"))
    )
    (comp (ref "R77")
      (value "10K")
      (footprint "eagle-import:R0603")
      (libsource (lib "eagle-import") (part "R-EU_R0603"))
    )
    (comp (ref "R78")
      (value "22R")
      (footprint "eagle-import:R0603")
      (libsource (lib "eagle-import") (part "R-EU_R0603"))
    )
    (comp (ref "R79")
      (value "10K")
      (footprint "eagle-import:R0603")
      (libsource (lib "eagle-import") (part "R-EU_R0603"))
    )
    (comp (ref "R80")
      (value "22R")
      (footprint "eagle-import:R0603")
      (libsource (lib "eagle-import") (part "R-EU_R0603"))
    )
    (comp (ref "R81")
      (value "10K")
      (footprint "eagle-import:R0603")
      (libsource (lib "eagle-import") (part "R-EU_R0603"))
    )
    (comp (ref "R82")
      (value "1K")
      (footprint "eagle-import:R0603")
      (libsource (lib "eagle-import") (part "R-EU_R0603"))
    )
    (comp (ref "R83")
      (value "10K")
      (footprint "eagle-import:R0603")
      (libsource (lib "eagle-import") (part "R-EU_R0603"))
    )
    (comp (ref "R88")
      (value "10K")
      (footprint "eagle-import:R0603")
      (libsource (lib "eagle-import") (part "R-EU_R0603"))
    )
    (comp (ref "R89")
      (value "10K")
      (footprint "eagle-import:R0603")
      (libsource (lib "eagle-import") (part "R-EU_R0603"))
    )
    (comp (ref "R90")
      (value "4K7")
      (footprint "eagle-import:R0603")
      (libsource (lib "eagle-import") (part "R-EU_R0603"))
    )
    (comp (ref "R91")
      (value "1K")
      (footprint "eagle-import:R0603")
      (libsource (lib "eagle-import") (part "R-EU_R0603"))
    )
    (comp (ref "R94")
      (value "1K5")
      (footprint "eagle-import:R0603")
      (libsource (lib "eagle-import") (part "R-EU_R0603"))
    )
    (comp (ref "R95")
      (value "1K5")
      (footprint "eagle-import:R0603")
      (libsource (lib "eagle-import") (part "R-EU_R0603"))
    )
    (comp (ref "R96")
      (value "1K5")
      (footprint "eagle-import:R0603")
      (libsource (lib "eagle-import") (part "R-EU_R0603"))
    )
    (comp (ref "R97")
      (value "VARISTORCN0603")
      (footprint "eagle-import:CT_CN0603")
      (libsource (lib "eagle-import") (part "VARISTORCN0603"))
    )
    (comp (ref "R98")
      (value "VARISTORCN0603")
      (footprint "eagle-import:CT_CN0603")
      (libsource (lib "eagle-import") (part "VARISTORCN0603"))
    )
    (comp (ref "RESET")
      (value "TAC_SWITCHSMD")
      (footprint "eagle-import:TACTILE_SWITCH_SMD")
      (libsource (lib "eagle-import") (part "TAC_SWITCHSMD"))
    )
    (comp (ref "RJ1")
      (value "ETHERNET")
      (footprint "eagle-import:J0011D21B")
      (libsource (lib "eagle-import") (part "J0011D21B"))
    )
    (comp (ref "RX")
      (value "LEDCHIPLED_0805")
      (footprint "eagle-import:CHIPLED_0805")
      (libsource (lib "eagle-import") (part "LEDCHIPLED_0805"))
    )
    (comp (ref "T1")
      (value "IRLML2246TRPBF")
      (footprint "eagle-import:SOT-23")
      (libsource (lib "eagle-import") (part "PMOSSOT23"))
    )
    (comp (ref "TX")
      (value "LEDCHIPLED_0805")
      (footprint "eagle-import:CHIPLED_0805")
      (libsource (lib "eagle-import") (part "LEDCHIPLED_0805"))
    )
    (comp (ref "T_E0")
      (value "22-23-2021")
      (footprint "eagle-import:22-23-2021")
      (fields (field (name "MF") "MOLEX"))
      (libsource (lib "eagle-import") (part "22-23-2021"))
    )
    (comp (ref "T_E1")
      (value "22-23-2021")
      (footprint "eagle-import:22-23-2021")
      (fields (field (name "MF") "MOLEX"))
      (libsource (lib "eagle-import") (part "22-23-2021"))
    )
    (comp (ref "T_HB")
      (value "22-23-2021")
      (footprint "eagle-import:22-23-2021")
      (fields (field (name "MF") "MOLEX"))
      (libsource (lib "eagle-import") (part "22-23-2021"))
    )
    (comp (ref "U$1")
      (value "USB+SHIELD")
      (footprint "eagle-import:USB-B-PTH")
      (libsource (lib "eagle-import") (part "USB+SHIELD"))
    )
    (comp (ref "U$3")
      (value "12Mhz")
      (footprint "eagle-import:CRYSTAL2734")
      (libsource (lib "eagle-import") (part "CRYSTAL2734"))
    )
    (comp (ref "U$7")
      (value "USB-MINIB-5PIN")
      (footprint "eagle-import:USB-MINIB")
      (libsource (lib "eagle-import") (part "USB-MINIB-5PIN"))
    )
    (comp (ref "U$8")
      (value "25Mhz")
      (footprint "eagle-import:CRYSTAL2734")
      (libsource (lib "eagle-import") (part "CRYSTAL2734"))
    )
    (comp (ref "U$17")
      (value "MOUNTINGHOLE3.0THIN")
      (footprint "eagle-import:MOUNTINGHOLE_3.0_PLATEDTHIN")
      (libsource (lib "eagle-import") (part "MOUNTINGHOLE3.0THIN"))
    )
    (comp (ref "U$18")
      (value "MOUNTINGHOLE3.0THIN")
      (footprint "eagle-import:MOUNTINGHOLE_3.0_PLATEDTHIN")
      (libsource (lib "eagle-import") (part "MOUNTINGHOLE3.0THIN"))
    )
    (comp (ref "U$20")
      (value "MOUNTINGHOLE3.0THIN")
      (footprint "eagle-import:MOUNTINGHOLE_3.0_PLATEDTHIN")
      (libsource (lib "eagle-import") (part "MOUNTINGHOLE3.0THIN"))
    )
    (comp (ref "U$21")
      (value "SUNLOGO")
      (footprint "eagle-import:SUN")
      (libsource (lib "eagle-import") (part "SUNLOGO"))
    )
    (comp (ref "U$22")
      (value "FIDUCIAL")
      (footprint "eagle-import:FIDUCIAL_1MM")
      (libsource (lib "eagle-import") (part "FIDUCIAL"))
    )
    (comp (ref "U$23")
      (value "FIDUCIAL")
      (footprint "eagle-import:FIDUCIAL_1MM")
      (libsource (lib "eagle-import") (part "FIDUCIAL"))
    )
    (comp (ref "U2")
      (value "USD-SOCKETNEW")
      (footprint "eagle-import:MICRO-SD-SOCKET-PP")
      (libsource (lib "eagle-import") (part "USD-SOCKETNEW"))
    )
    (comp (ref "U3")
      (value "LAN8720")
      (footprint "eagle-import:QFN24_4MM")
      (libsource (lib "eagle-import") (part "LAN8720"))
    )
    (comp (ref "U4")
      (value "74LVC1G04")
      (footprint "eagle-import:SOT23-5")
      (libsource (lib "eagle-import") (part "74LVC1G04"))
    )
    (comp (ref "V_HEAT")
      (value "HEATERS")
      (footprint "eagle-import:W237-102")
      (fields (field (name "MPN") "237-102"))
      (libsource (lib "eagle-import") (part "W237-102"))
    )
    (comp (ref "V_MOT")
      (value "MOTORS")
      (footprint "eagle-import:W237-102")
      (fields (field (name "MPN") "237-102"))
      (libsource (lib "eagle-import") (part "W237-102"))
    )
    (comp (ref "X_AXIS")
      (value "22-23-2041")
      (footprint "eagle-import:22-23-2041")
      (fields (field (name "MF") "MOLEX"))
      (libsource (lib "eagle-import") (part "22-23-2041"))
    )
    (comp (ref "X_MAX")
      (value "22-23-2031")
      (footprint "eagle-import:22-23-2031")
      (fields
        (field (name "MF") "MOLEX")
        (field (name "MF_1") "MOLEX")
        (field (name "MPN") "22-23-2031")
        (field (name "OC_FARNELL") "1462950")
        (field (name "OC_NEWARK") "30C0862")
      )
      (libsource (lib "eagle-import") (part "22-23-2031"))
    )
    (comp (ref "X_MIN")
      (value "22-23-2031")
      (footprint "eagle-import:22-23-2031")
      (fields (field (name "MF") "MOLEX"))
      (libsource (lib "eagle-import") (part "22-23-2031"))
    )
    (comp (ref "Y_AXIS")
      (value "22-23-2041")
      (footprint "eagle-import:22-23-2041")
      (fields (field (name "MF") "MOLEX"))
      (libsource (lib "eagle-import") (part "22-23-2041"))
    )
    (comp (ref "Y_MAX")
      (value "22-23-2031")
      (footprint "eagle-import:22-23-2031")
      (fields
        (field (name "MF") "MOLEX")
        (field (name "MF_1") "MOLEX")
        (field (name "MPN") "22-23-2031")
        (field (name "OC_FARNELL") "1462950")
        (field (name "OC_NEWARK") "30C0862")
      )
      (libsource (lib "eagle-import") (part "22-23-2031"))
    )
    (comp (ref "Y_MIN")
      (value "22-23-2031")
      (footprint "eagle-import:22-23-2031")
      (fields (field (name "MF") "MOLEX"))
      (libsource (lib "eagle-import") (part "22-23-2031"))
    )
    (comp (ref "Z_AXIS")
      (value "22-23-2041")
      (footprint "eagle-import:22-23-2041")
      (fields (field (name "MF") "MOLEX"))
      (libsource (lib "eagle-import") (part "22-23-2041"))
    )
    (comp (ref "Z_MAX")
      (value "22-23-2031")
      (footprint "eagle-import:22-23-2031")
      (fields
        (field (name "MF") "MOLEX")
        (field (name "MF_1") "MOLEX")
        (field (name "MPN") "22-23-2031")
        (field (name "OC_FARNELL") "1462950")
        (field (name "OC_NEWARK") "30C0862")
      )
      (libsource (lib "eagle-import") (part "22-23-2031"))
    )
    (comp (ref "Z_MIN")
      (value "22-23-2031")
      (footprint "eagle-import:22-23-2031")
      (fields (field (name "MF") "MOLEX"))
      (libsource (lib "eagle-import") (part "22-23-2031"))
    )
  )
  (nets
    (net (code "1") (name "+3V3") (class "Default")
      (node (ref "AD5206") (pin "6") (pinfunction "VDD_6") (pintype "bidirectional"))
      (node (ref "C10") (pin "1") (pinfunction "1_1") (pintype "passive"))
      (node (ref "C11") (pin "A") (pinfunction "+_A") (pintype "passive"))
      (node (ref "C14") (pin "A") (pinfunction "+_A") (pintype "passive"))
      (node (ref "C17") (pin "1") (pinfunction "1_1") (pintype "passive"))
      (node (ref "C19") (pin "2") (pinfunction "2_2") (pintype "passive"))
      (node (ref "C29") (pin "2") (pinfunction "2_2") (pintype "passive"))
      (node (ref "C36") (pin "2") (pinfunction "2_2") (pintype "passive"))
      (node (ref "C4") (pin "1") (pinfunction "1_1") (pintype "passive"))
      (node (ref "C43") (pin "2") (pinfunction "2_2") (pintype "passive"))
      (node (ref "C5") (pin "1") (pinfunction "1_1") (pintype "passive"))
      (node (ref "C50") (pin "2") (pinfunction "2_2") (pintype "passive"))
      (node (ref "C59") (pin "1") (pinfunction "1_1") (pintype "passive"))
      (node (ref "C6") (pin "1") (pinfunction "1_1") (pintype "passive"))
      (node (ref "C61") (pin "A") (pinfunction "+_A") (pintype "passive"))
      (node (ref "C63") (pin "1") (pinfunction "1_1") (pintype "passive"))
      (node (ref "C7") (pin "1") (pinfunction "1_1") (pintype "passive"))
      (node (ref "C70") (pin "1") (pinfunction "1_1") (pintype "passive"))
      (node (ref "C71") (pin "1") (pinfunction "1_1") (pintype "passive"))
      (node (ref "C79") (pin "1") (pinfunction "1_1") (pintype "passive"))
      (node (ref "C8") (pin "1") (pinfunction "1_1") (pintype "passive"))
      (node (ref "C9") (pin "1") (pinfunction "1_1") (pintype "passive"))
      (node (ref "END_STOP_V") (pin "3") (pinfunction "3_3") (pintype "passive"))
      (node (ref "FB1") (pin "1") (pinfunction "P$1_1") (pintype "passive"))
      (node (ref "FB2") (pin "1") (pinfunction "P$1_1") (pintype "passive"))
      (node (ref "IC10") (pin "2") (pinfunction "OUT_2") (pintype "passive"))
      (node (ref "IC10") (pin "TAB") (pinfunction "OUT1_TAB") (pintype "passive"))
      (node (ref "IC2") (pin "15") (pinfunction "VDD_15") (pintype "power_in"))
      (node (ref "IC3") (pin "15") (pinfunction "VDD_15") (pintype "power_in"))
      (node (ref "IC4") (pin "15") (pinfunction "VDD_15") (pintype "power_in"))
      (node (ref "IC5") (pin "15") (pinfunction "VDD_15") (pintype "power_in"))
      (node (ref "IC6") (pin "15") (pinfunction "VDD_15") (pintype "power_in"))
      (node (ref "L2") (pin "2") (pinfunction "2_2") (pintype "passive"))
      (node (ref "LPC1769") (pin "19") (pinfunction "VBAT_19") (pintype "power_in"))
      (node (ref "LPC1769") (pin "28") (pinfunction "VDD(3V3)1_28") (pintype "power_in"))
      (node (ref "LPC1769") (pin "42") (pinfunction "VDD(REG)(3V3)1_42") (pintype "power_in"))
      (node (ref "LPC1769") (pin "54") (pinfunction "VDD(3V3)2_54") (pintype "power_in"))
      (node (ref "LPC1769") (pin "71") (pinfunction "VDD(3V3)3_71") (pintype "power_in"))
      (node (ref "LPC1769") (pin "84") (pinfunction "VDD(REG)(3V3)2_84") (pintype "power_in"))
      (node (ref "LPC1769") (pin "96") (pinfunction "VDD(3V3)4_96") (pintype "power_in"))
      (node (ref "Q1") (pin "E") (pinfunction "E_E") (pintype "passive"))
      (node (ref "R10") (pin "1") (pinfunction "1_1") (pintype "passive"))
      (node (ref "R14") (pin "2") (pinfunction "2_2") (pintype "passive"))
      (node (ref "R22") (pin "2") (pinfunction "2_2") (pintype "passive"))
      (node (ref "R23") (pin "2") (pinfunction "2_2") (pintype "passive"))
      (node (ref "R24") (pin "2") (pinfunction "2_2") (pintype "passive"))
      (node (ref "R25") (pin "1") (pinfunction "1_1") (pintype "passive"))
      (node (ref "R26") (pin "1") (pinfunction "1_1") (pintype "passive"))
      (node (ref "R27") (pin "1") (pinfunction "1_1") (pintype "passive"))
      (node (ref "R31") (pin "2") (pinfunction "2_2") (pintype "passive"))
      (node (ref "R33") (pin "1") (pinfunction "1_1") (pintype "passive"))
      (node (ref "R34") (pin "1") (pinfunction "1_1") (pintype "passive"))
      (node (ref "R35") (pin "1") (pinfunction "1_1") (pintype "passive"))
      (node (ref "R39") (pin "2") (pinfunction "2_2") (pintype "passive"))
      (node (ref "R4") (pin "1") (pinfunction "1_1") (pintype "passive"))
      (node (ref "R41") (pin "1") (pinfunction "1_1") (pintype "passive"))
      (node (ref "R42") (pin "1") (pinfunction "1_1") (pintype "passive"))
      (node (ref "R43") (pin "1") (pinfunction "1_1") (pintype "passive"))
      (node (ref "R47") (pin "2") (pinfunction "2_2") (pintype "passive"))
      (node (ref "R49") (pin "1") (pinfunction "1_1") (pintype "passive"))
      (node (ref "R5") (pin "2") (pinfunction "2_2") (pintype "passive"))
      (node (ref "R50") (pin "1") (pinfunction "1_1") (pintype "passive"))
      (node (ref "R51") (pin "1") (pinfunction "1_1") (pintype "passive"))
      (node (ref "R55") (pin "2") (pinfunction "2_2") (pintype "passive"))
      (node (ref "R57") (pin "1") (pinfunction "1_1") (pintype "passive"))
      (node (ref "R58") (pin "1") (pinfunction "1_1") (pintype "passive"))
      (node (ref "R6") (pin "2") (pinfunction "2_2") (pintype "passive"))
      (node (ref "R64") (pin "1") (pinfunction "1_1") (pintype "passive"))
      (node (ref "R65") (pin "1") (pinfunction "1_1") (pintype "passive"))
      (node (ref "R66") (pin "1") (pinfunction "1_1") (pintype "passive"))
      (node (ref "R67") (pin "1") (pinfunction "1_1") (pintype "passive"))
      (node (ref "R7") (pin "2") (pinfunction "2_2") (pintype "passive"))
      (node (ref "R70") (pin "2") (pinfunction "2_2") (pintype "passive"))
      (node (ref "R71") (pin "2") (pinfunction "2_2") (pintype "passive"))
      (node (ref "R72") (pin "2") (pinfunction "2_2") (pintype "passive"))
      (node (ref "R74") (pin "1") (pinfunction "1_1") (pintype "passive"))
      (node (ref "R75") (pin "1") (pinfunction "1_1") (pintype "passive"))
      (node (ref "R8") (pin "1") (pinfunction "1_1") (pintype "passive"))
      (node (ref "R83") (pin "2") (pinfunction "2_2") (pintype "passive"))
      (node (ref "R88") (pin "2") (pinfunction "2_2") (pintype "passive"))
      (node (ref "R9") (pin "1") (pinfunction "1_1") (pintype "passive"))
      (node (ref "U2") (pin "4") (pinfunction "VCC_4") (pintype "bidirectional"))
      (node (ref "U3") (pin "9") (pinfunction "VDDIO_9") (pintype "bidirectional"))
      (node (ref "U4") (pin "5") (pinfunction "VCC_5") (pintype "power_in"))
    )
    (net (code "2") (name "/1,65V") (class "Default")
      (node (ref "IC9") (pin "2") (pinfunction "-IN_2") (pintype "input"))
      (node (ref "R88") (pin "1") (pinfunction "1_1") (pintype "passive"))
      (node (ref "R89") (pin "1") (pinfunction "1_1") (pintype "passive"))
    )
    (net (code "3") (name "/B_THERM") (class "Default")
      (node (ref "C27") (pin "2") (pinfunction "2_2") (pintype "passive"))
      (node (ref "LPC1769") (pin "7") (pinfunction "P0[25]/AD0[2]/I2SRX_SDA/TXD3_7") (pintype "bidirectional"))
      (node (ref "R24") (pin "1") (pinfunction "1_1") (pintype "passive"))
      (node (ref "T_HB") (pin "2") (pinfunction "S_2") (pintype "passive"))
    )
    (net (code "4") (name "/D+") (class "Default")
      (node (ref "R1") (pin "1") (pinfunction "1_1") (pintype "passive"))
      (node (ref "R98") (pin "1") (pinfunction "1_1") (pintype "passive"))
      (node (ref "U$1") (pin "D+") (pinfunction "D+_D+") (pintype "bidirectional"))
    )
    (net (code "5") (name "/D-") (class "Default")
      (node (ref "R2") (pin "1") (pinfunction "1_1") (pintype "passive"))
      (node (ref "R97") (pin "1") (pinfunction "1_1") (pintype "passive"))
      (node (ref "U$1") (pin "D-") (pinfunction "D-_D-") (pintype "bidirectional"))
    )
    (net (code "6") (name "/DIR_E0") (class "Default")
      (node (ref "IC2") (pin "19") (pinfunction "DIR_19") (pintype "input"))
      (node (ref "LPC1769") (pin "56") (pinfunction "P0[22]/RTS1/TD1_56") (pintype "bidirectional"))
    )
    (net (code "7") (name "/DIR_E1") (class "Default")
      (node (ref "IC6") (pin "19") (pinfunction "DIR_19") (pintype "input"))
      (node (ref "LPC1769") (pin "37") (pinfunction "P1[23]/MCFB1/PWM1[4]/MISO0_37") (pintype "bidirectional"))
    )
    (net (code "8") (name "/DIR_X") (class "Default")
      (node (ref "IC5") (pin "19") (pinfunction "DIR_19") (pintype "input"))
      (node (ref "LPC1769") (pin "80") (pinfunction "P0[5]/I2SRX_WS/TD2/CAP2[1]_80") (pintype "bidirectional"))
    )
    (net (code "9") (name "/DIR_Y") (class "Default")
      (node (ref "IC4") (pin "19") (pinfunction "DIR_19") (pintype "input"))
      (node (ref "LPC1769") (pin "49") (pinfunction "P0[11]/RXD2/SCL2/MAT3[1]_49") (pintype "bidirectional"))
    )
    (net (code "10") (name "/DIR_Z") (class "Default")
      (node (ref "IC3") (pin "19") (pinfunction "DIR_19") (pintype "input"))
      (node (ref "LPC1769") (pin "58") (pinfunction "P0[20]/DTR1/SCL1_58") (pintype "bidirectional"))
    )
    (net (code "11") (name "/E0_H") (class "Default")
      (node (ref "FET_DRV1") (pin "2") (pinfunction "P$1_2") (pintype "bidirectional"))
      (node (ref "LPC1769") (pin "68") (pinfunction "P2[5]/PWM1[6]/DTR1/TRACEDATA[0]_68") (pintype "bidirectional"))
      (node (ref "R77") (pin "1") (pinfunction "1_1") (pintype "passive"))
    )
    (net (code "12") (name "/E0_THERM") (class "Default")
      (node (ref "C25") (pin "2") (pinfunction "2_2") (pintype "passive"))
      (node (ref "LPC1769") (pin "9") (pinfunction "P0[23]/AD0[0]/I2SRX_CLK/CAP3[0]_9") (pintype "bidirectional"))
      (node (ref "R22") (pin "1") (pinfunction "1_1") (pintype "passive"))
      (node (ref "T_E0") (pin "2") (pinfunction "S_2") (pintype "passive"))
    )
    (net (code "13") (name "/E1_H") (class "Default")
      (node (ref "FET_DRV1") (pin "4") (pinfunction "P$1_4") (pintype "bidirectional"))
      (node (ref "LPC1769") (pin "67") (pinfunction "P2[6]/PCAP1[0]/RI1/TRACECLK_67") (pintype "bidirectional"))
      (node (ref "R79") (pin "1") (pinfunction "1_1") (pintype "passive"))
    )
    (net (code "14") (name "/E1_THERM") (class "Default")
      (node (ref "C26") (pin "2") (pinfunction "2_2") (pintype "passive"))
      (node (ref "LPC1769") (pin "8") (pinfunction "P0[24]/AD0[1]/I2SRX_WS/CAP3[1]_8") (pintype "bidirectional"))
      (node (ref "R23") (pin "1") (pinfunction "1_1") (pintype "passive"))
      (node (ref "T_E1") (pin "2") (pinfunction "S_2") (pintype "passive"))
    )
    (net (code "15") (name "/ENABLE_E0") (class "Default")
      (node (ref "IC2") (pin "2") (pinfunction "ENABLE_2") (pintype "input"))
      (node (ref "LPC1769") (pin "57") (pinfunction "P0[21]/RI1/RD1_57") (pintype "bidirectional"))
    )
    (net (code "16") (name "/ENABLE_E1") (class "Default")
      (node (ref "IC6") (pin "2") (pinfunction "ENABLE_2") (pintype "input"))
      (node (ref "LPC1769") (pin "36") (pinfunction "P1[22]/MC0B/USB_PWRD/MAT1[0]_36") (pintype "bidirectional"))
    )
    (net (code "17") (name "/ENABLE_X") (class "Default")
      (node (ref "IC5") (pin "2") (pinfunction "ENABLE_2") (pintype "input"))
      (node (ref "LPC1769") (pin "81") (pinfunction "P0[4]/I2SRX_CLK/RD2/CAP2[0]_81") (pintype "bidirectional"))
    )
    (net (code "18") (name "/ENABLE_Y") (class "Default")
      (node (ref "IC4") (pin "2") (pinfunction "ENABLE_2") (pintype "input"))
      (node (ref "LPC1769") (pin "48") (pinfunction "P0[10]/TXD2/SDA2/MAT3[0]_48") (pintype "bidirectional"))
    )
    (net (code "19") (name "/ENABLE_Z") (class "Default")
      (node (ref "IC3") (pin "2") (pinfunction "ENABLE_2") (pintype "input"))
      (node (ref "LPC1769") (pin "59") (pinfunction "P0[19]/DSR1/SDA1_59") (pintype "bidirectional"))
    )
    (net (code "20") (name "/ENC1") (class "Default")
      (node (ref "LPC1769") (pin "21") (pinfunction "P1[30]/VBUS/AD0[4]_21") (pintype "bidirectional"))
      (node (ref "PANEL") (pin "6") (pinfunction "KL_6") (pintype "passive"))
    )
    (net (code "21") (name "/ENC2") (class "Default")
      (node (ref "LPC1769") (pin "20") (pinfunction "P1[31]/SCK1/AD0[5]_20") (pintype "bidirectional"))
      (node (ref "PANEL") (pin "5") (pinfunction "KL_5") (pintype "passive"))
    )
    (net (code "22") (name "/ENC_CLK") (class "Default")
      (node (ref "LPC1769") (pin "52") (pinfunction "P2[11]/EINT1/I2STX_CLK_52") (pintype "bidirectional"))
      (node (ref "PANEL") (pin "8") (pinfunction "KL_8") (pintype "passive"))
    )
    (net (code "23") (name "/ENET_CRS") (class "Default")
      (node (ref "LPC1769") (pin "92") (pinfunction "P1[8]/ENET_CRS_92") (pintype "bidirectional"))
      (node (ref "R61") (pin "2") (pinfunction "2_2") (pintype "passive"))
    )
    (net (code "24") (name "/ENET_MDC") (class "Default")
      (node (ref "LPC1769") (pin "87") (pinfunction "P1[16]/ENET_MDC_87") (pintype "bidirectional"))
      (node (ref "U3") (pin "13") (pinfunction "MDC_13") (pintype "bidirectional"))
    )
    (net (code "25") (name "/ENET_MDIO") (class "Default")
      (node (ref "LPC1769") (pin "86") (pinfunction "P1[17]/ENET_MDIO_86") (pintype "bidirectional"))
      (node (ref "R57") (pin "2") (pinfunction "2_2") (pintype "passive"))
      (node (ref "U3") (pin "12") (pinfunction "MDIO_12") (pintype "bidirectional"))
    )
    (net (code "26") (name "/ENET_REF_CLK") (class "Default")
      (node (ref "LPC1769") (pin "88") (pinfunction "P1[15]/ENET_REF_CLK_88") (pintype "bidirectional"))
      (node (ref "U4") (pin "4") (pinfunction "Y_4") (pintype "bidirectional"))
    )
    (net (code "27") (name "/ENET_RXD0") (class "Default")
      (node (ref "LPC1769") (pin "91") (pinfunction "P1[9]/ENET_RXD0_91") (pintype "bidirectional"))
      (node (ref "R59") (pin "2") (pinfunction "2_2") (pintype "passive"))
    )
    (net (code "28") (name "/ENET_RXD1") (class "Default")
      (node (ref "LPC1769") (pin "90") (pinfunction "P1[10]/ENET_RXD1_90") (pintype "bidirectional"))
      (node (ref "R60") (pin "2") (pinfunction "2_2") (pintype "passive"))
    )
    (net (code "29") (name "/ENET_RX_ER") (class "Default")
      (node (ref "LPC1769") (pin "89") (pinfunction "P1[14]/ENET_RX_ER_89") (pintype "bidirectional"))
      (node (ref "R58") (pin "2") (pinfunction "2_2") (pintype "passive"))
      (node (ref "U3") (pin "10") (pinfunction "RXER_10") (pintype "bidirectional"))
    )
    (net (code "30") (name "/ENET_TXD0") (class "Default")
      (node (ref "LPC1769") (pin "95") (pinfunction "P1[0]/ENET_TXD0_95") (pintype "bidirectional"))
      (node (ref "U3") (pin "17") (pinfunction "TXD0_17") (pintype "bidirectional"))
    )
    (net (code "31") (name "/ENET_TXD1") (class "Default")
      (node (ref "LPC1769") (pin "94") (pinfunction "P1[1]/ENET_TXD1_94") (pintype "bidirectional"))
      (node (ref "U3") (pin "18") (pinfunction "TXD1_18") (pintype "bidirectional"))
    )
    (net (code "32") (name "/ENET_TX_EN") (class "Default")
      (node (ref "LPC1769") (pin "93") (pinfunction "P1[4]/ENET_TX_EN_93") (pintype "bidirectional"))
      (node (ref "U3") (pin "16") (pinfunction "TXEN_16") (pintype "bidirectional"))
    )
    (net (code "33") (name "/FAN1") (class "Default")
      (node (ref "LPC1769") (pin "32") (pinfunction "P1[18]/USB_UP_LED/PWM1[1]/CAP1[0]_32") (pintype "bidirectional"))
      (node (ref "Q2") (pin "G") (pinfunction "G_G") (pintype "passive"))
      (node (ref "R16") (pin "2") (pinfunction "2_2") (pintype "passive"))
    )
    (net (code "34") (name "/FAN2") (class "Default")
      (node (ref "LPC1769") (pin "33") (pinfunction "P1[19]/MC0A/USB_PPWR/CAP1[1]_33") (pintype "bidirectional"))
      (node (ref "Q3") (pin "G") (pinfunction "G_G") (pintype "passive"))
      (node (ref "R18") (pin "2") (pinfunction "2_2") (pintype "passive"))
    )
    (net (code "35") (name "/FAN3") (class "Default")
      (node (ref "LPC1769") (pin "34") (pinfunction "P1[20]/MCFB0/PWM1[2]/SCK0_34") (pintype "bidirectional"))
      (node (ref "Q4") (pin "G") (pinfunction "G_G") (pintype "passive"))
      (node (ref "R20") (pin "2") (pinfunction "2_2") (pintype "passive"))
    )
    (net (code "36") (name "/HB_H") (class "Default")
      (node (ref "FET_DRV2") (pin "2") (pinfunction "P$1_2") (pintype "bidirectional"))
      (node (ref "LPC1769") (pin "66") (pinfunction "P2[7]/RD2/RTS1_66") (pintype "bidirectional"))
      (node (ref "R81") (pin "1") (pinfunction "1_1") (pintype "passive"))
    )
    (net (code "37") (name "/JTAG-RTCK") (class "Default")
      (node (ref "LPC1769") (pin "100") (pinfunction "RTCK_100") (pintype "bidirectional"))
    )
    (net (code "38") (name "/JTAG-TCK") (class "Default")
      (node (ref "LPC1769") (pin "5") (pinfunction "TCK/SWDCLK_5") (pintype "bidirectional"))
    )
    (net (code "39") (name "/JTAG-TDI") (class "Default")
      (node (ref "LPC1769") (pin "2") (pinfunction "TDI_2") (pintype "bidirectional"))
    )
    (net (code "40") (name "/JTAG-TDO") (class "Default")
      (node (ref "LPC1769") (pin "1") (pinfunction "TDO/SWO_1") (pintype "bidirectional"))
    )
    (net (code "41") (name "/JTAG-TMS") (class "Default")
      (node (ref "LPC1769") (pin "3") (pinfunction "TMS/SWDIO_3") (pintype "bidirectional"))
    )
    (net (code "42") (name "/JTAG-TRST") (class "Default")
      (node (ref "LPC1769") (pin "4") (pinfunction "TRST_4") (pintype "bidirectional"))
    )
    (net (code "43") (name "/LCD_A0") (class "Default")
      (node (ref "LPC1769") (pin "50") (pinfunction "P2[13]/EINT3/I2STX_SDA_50") (pintype "bidirectional"))
      (node (ref "PANEL") (pin "16") (pinfunction "KL_16") (pintype "passive"))
    )
    (net (code "44") (name "/LCD_CS") (class "Default")
      (node (ref "LPC1769") (pin "63") (pinfunction "P0[16]/RXD1/SSEL0/SSEL_63") (pintype "bidirectional"))
      (node (ref "PANEL") (pin "18") (pinfunction "KL_18") (pintype "passive"))
    )
    (net (code "45") (name "/LCD_MISO") (class "Default")
      (node (ref "LPC1769") (pin "61") (pinfunction "P0[17]/CTS1/MISO0/MISO_61") (pintype "bidirectional"))
      (node (ref "PANEL") (pin "13") (pinfunction "KL_13") (pintype "passive"))
    )
    (net (code "46") (name "/LCD_MOSI") (class "Default")
      (node (ref "LPC1769") (pin "60") (pinfunction "P0[18]/DCD1/MOSI0/MOSI_60") (pintype "bidirectional"))
      (node (ref "PANEL") (pin "14") (pinfunction "KL_14") (pintype "passive"))
    )
    (net (code "47") (name "/LCD_RST") (class "Default")
      (node (ref "LPC1769") (pin "65") (pinfunction "P2[8]/TD2/TXD2_65") (pintype "bidirectional"))
      (node (ref "PANEL") (pin "17") (pinfunction "KL_17") (pintype "passive"))
    )
    (net (code "48") (name "/LCD_SCK") (class "Default")
      (node (ref "LPC1769") (pin "62") (pinfunction "P0[15]/TXD1/SCK0/SCK_62") (pintype "bidirectional"))
      (node (ref "PANEL") (pin "15") (pinfunction "KL_15") (pintype "passive"))
    )
    (net (code "49") (name "/LED1{slash}REGOFF") (class "Default")
      (node (ref "RJ1") (pin "G") (pinfunction "G_G") (pintype "bidirectional"))
      (node (ref "U3") (pin "3") (pinfunction "LED1/REGOFF_3") (pintype "bidirectional"))
    )
    (net (code "50") (name "/LED2{slash}NINTSEL") (class "Default")
      (node (ref "RJ1") (pin "Y") (pinfunction "Y_Y") (pintype "bidirectional"))
      (node (ref "U3") (pin "2") (pinfunction "LED2/NINTSEL_2") (pintype "bidirectional"))
    )
    (net (code "51") (name "/N$35") (class "Default")
      (node (ref "LPC1769") (pin "26") (pinfunction "P3[26]/STCLK/MAT0[1]/PWM1[3]_26") (pintype "bidirectional"))
    )
    (net (code "52") (name "/N$40") (class "Default")
      (node (ref "LPC1769") (pin "6") (pinfunction "P0[26]/AD0[3]/AOUT/RXD3_6") (pintype "bidirectional"))
    )
    (net (code "53") (name "/N$140") (class "Default")
      (node (ref "LPC1769") (pin "82") (pinfunction "P4[28]/RX_MCLK/MAT2[0]/TXD3_82") (pintype "bidirectional"))
    )
    (net (code "54") (name "/N$147") (class "Default")
      (node (ref "PANEL") (pin "12") (pinfunction "KL_12") (pintype "passive"))
    )
    (net (code "55") (name "/N$156") (class "Default")
      (node (ref "PANEL") (pin "11") (pinfunction "KL_11") (pintype "passive"))
    )
    (net (code "56") (name "/N$160") (class "Default")
      (node (ref "PANEL") (pin "19") (pinfunction "KL_19") (pintype "passive"))
    )
    (net (code "57") (name "/P2.9") (class "Default")
      (node (ref "LPC1769") (pin "64") (pinfunction "P2[9]/USB_CONNECT/RXD2_64") (pintype "bidirectional"))
      (node (ref "R3") (pin "1") (pinfunction "1_1") (pintype "passive"))
    )
    (net (code "58") (name "/PEN_IRQ") (class "Default")
      (node (ref "LPC1769") (pin "27") (pinfunction "P3[25]/MAT0[0]/PWM1[2]_27") (pintype "bidirectional"))
      (node (ref "PANEL") (pin "4") (pinfunction "KL_4") (pintype "passive"))
    )
    (net (code "59") (name "/PLAY") (class "Default")
      (node (ref "LPC1769") (pin "51") (pinfunction "P2[12]/EINT2/I2STX_WS_51") (pintype "bidirectional"))
      (node (ref "PANEL") (pin "20") (pinfunction "KL_20") (pintype "passive"))
      (node (ref "PLAY") (pin "1") (pinfunction "1_1") (pintype "passive"))
      (node (ref "PLAY") (pin "2") (pinfunction "2_2") (pintype "passive"))
      (node (ref "R71") (pin "1") (pinfunction "1_1") (pintype "passive"))
    )
    (net (code "60") (name "/POT_CS") (class "Default")
      (node (ref "AD5206") (pin "5") (pinfunction "~{CS}_5") (pintype "bidirectional"))
      (node (ref "LPC1769") (pin "85") (pinfunction "P4[29]/TX_MCLK/MAT2[1]/RXD3_85") (pintype "bidirectional"))
    )
    (net (code "61") (name "/POT_SCL") (class "Default")
      (node (ref "LPC1769") (pin "24") (pinfunction "P0[28]/SCL0/USB_SCL_24") (pintype "bidirectional"))
    )
    (net (code "62") (name "/POT_SDA") (class "Default")
      (node (ref "LPC1769") (pin "25") (pinfunction "P0[27]/SDA0/USB_SDA_25") (pintype "bidirectional"))
    )
    (net (code "63") (name "/PROGRAM") (class "Default")
      (node (ref "LPC1769") (pin "53") (pinfunction "P2[10]/EINT0/NMI_53") (pintype "bidirectional"))
      (node (ref "PROGRAM") (pin "1") (pinfunction "1_1") (pintype "passive"))
      (node (ref "PROGRAM") (pin "2") (pinfunction "2_2") (pintype "passive"))
      (node (ref "R72") (pin "1") (pinfunction "1_1") (pintype "passive"))
    )
    (net (code "64") (name "/P_LED") (class "Default")
      (node (ref "PANEL") (pin "3") (pinfunction "KL_3") (pintype "passive"))
    )
    (net (code "65") (name "/REF_E0") (class "Default")
      (node (ref "AD5206") (pin "17") (pinfunction "W1_17") (pintype "bidirectional"))
      (node (ref "IC2") (pin "17") (pinfunction "REF_17") (pintype "input"))
    )
    (net (code "66") (name "/REF_E1") (class "Default")
      (node (ref "AD5206") (pin "14") (pinfunction "W3_14") (pintype "bidirectional"))
      (node (ref "IC6") (pin "17") (pinfunction "REF_17") (pintype "input"))
    )
    (net (code "67") (name "/REF_X") (class "Default")
      (node (ref "AD5206") (pin "2") (pinfunction "W6_2") (pintype "bidirectional"))
      (node (ref "IC5") (pin "17") (pinfunction "REF_17") (pintype "input"))
    )
    (net (code "68") (name "/REF_Y") (class "Default")
      (node (ref "AD5206") (pin "23") (pinfunction "W4_23") (pintype "bidirectional"))
      (node (ref "IC4") (pin "17") (pinfunction "REF_17") (pintype "input"))
    )
    (net (code "69") (name "/REF_Z") (class "Default")
      (node (ref "AD5206") (pin "20") (pinfunction "W2_20") (pintype "bidirectional"))
      (node (ref "IC3") (pin "17") (pinfunction "REF_17") (pintype "input"))
    )
    (net (code "70") (name "/RESET") (class "Default")
      (node (ref "LPC1769") (pin "17") (pinfunction "RESET_17") (pintype "bidirectional"))
      (node (ref "PANEL") (pin "7") (pinfunction "KL_7") (pintype "passive"))
      (node (ref "R70") (pin "1") (pinfunction "1_1") (pintype "passive"))
      (node (ref "RESET") (pin "1") (pinfunction "1_1") (pintype "passive"))
      (node (ref "RESET") (pin "2") (pinfunction "2_2") (pintype "passive"))
    )
    (net (code "71") (name "/RSTOUT") (class "Default")
      (node (ref "LPC1769") (pin "14") (pinfunction "RSTOUT_14") (pintype "bidirectional"))
      (node (ref "U3") (pin "15") (pinfunction "NRST_15") (pintype "bidirectional"))
    )
    (net (code "72") (name "/RX_0") (class "Default")
      (node (ref "IC7") (pin "1") (pinfunction "TXD_1") (pintype "output"))
      (node (ref "LPC1769") (pin "99") (pinfunction "P0[3]/RXD0/AD0[6]_99") (pintype "bidirectional"))
    )
    (net (code "73") (name "/SCL") (class "Default")
      (node (ref "LPC1769") (pin "47") (pinfunction "P0[1]/TD1/RXD3/SCL1_47") (pintype "bidirectional"))
      (node (ref "PANEL") (pin "9") (pinfunction "KL_9") (pintype "passive"))
    )
    (net (code "74") (name "/SDA") (class "Default")
      (node (ref "LPC1769") (pin "46") (pinfunction "P0[0]/RD1/TXD3/SDA1_46") (pintype "bidirectional"))
      (node (ref "PANEL") (pin "10") (pinfunction "KL_10") (pintype "passive"))
    )
    (net (code "75") (name "/SD_CS") (class "Default")
      (node (ref "LPC1769") (pin "79") (pinfunction "P0[6]/I2SRX_SDA/SSEL1/MAT2[0]_79") (pintype "bidirectional"))
      (node (ref "R7") (pin "1") (pinfunction "1_1") (pintype "passive"))
      (node (ref "U2") (pin "2") (pinfunction "CS_2") (pintype "bidirectional"))
    )
    (net (code "76") (name "/SD_MISO") (class "Default")
      (node (ref "LPC1769") (pin "77") (pinfunction "P0[8]/I2STX_WS/MISO1/MAT2[2]_77") (pintype "bidirectional"))
      (node (ref "R6") (pin "1") (pinfunction "1_1") (pintype "passive"))
      (node (ref "U2") (pin "7") (pinfunction "DO_7") (pintype "bidirectional"))
    )
    (net (code "77") (name "/SD_MOSI") (class "Default")
      (node (ref "AD5206") (pin "7") (pinfunction "SDI_7") (pintype "bidirectional"))
      (node (ref "LPC1769") (pin "76") (pinfunction "P0[9]/I2STX_SDA/MOSI1/MAT2[3]_76") (pintype "bidirectional"))
      (node (ref "R5") (pin "1") (pinfunction "1_1") (pintype "passive"))
      (node (ref "U2") (pin "3") (pinfunction "DI_3") (pintype "bidirectional"))
    )
    (net (code "78") (name "/SD_SCK") (class "Default")
      (node (ref "AD5206") (pin "8") (pinfunction "CLK_8") (pintype "bidirectional"))
      (node (ref "LPC1769") (pin "78") (pinfunction "P0[7]/I2STX_CLK/SCK1/MAT2[1]_78") (pintype "bidirectional"))
      (node (ref "U2") (pin "5") (pinfunction "SCK_5") (pintype "bidirectional"))
    )
    (net (code "79") (name "/STEP_E0") (class "Default")
      (node (ref "IC2") (pin "16") (pinfunction "STEP_16") (pintype "input"))
      (node (ref "LPC1769") (pin "70") (pinfunction "P2[3]/PWM1[4]/DCD1/TRACEDATA[2]_70") (pintype "bidirectional"))
    )
    (net (code "80") (name "/STEP_E1") (class "Default")
      (node (ref "IC6") (pin "16") (pinfunction "STEP_16") (pintype "input"))
      (node (ref "LPC1769") (pin "69") (pinfunction "P2[4]/PWM1[5]/DSR1/TRACEDATA[1]_69") (pintype "bidirectional"))
    )
    (net (code "81") (name "/STEP_X") (class "Default")
      (node (ref "IC5") (pin "16") (pinfunction "STEP_16") (pintype "input"))
      (node (ref "LPC1769") (pin "75") (pinfunction "P2[0]/PWM1[1]/TXD1_75") (pintype "bidirectional"))
    )
    (net (code "82") (name "/STEP_Y") (class "Default")
      (node (ref "IC4") (pin "16") (pinfunction "STEP_16") (pintype "input"))
      (node (ref "LPC1769") (pin "74") (pinfunction "P2[1]/PWM1[2]/RXD1_74") (pintype "bidirectional"))
    )
    (net (code "83") (name "/STEP_Z") (class "Default")
      (node (ref "IC3") (pin "16") (pinfunction "STEP_16") (pintype "input"))
      (node (ref "LPC1769") (pin "73") (pinfunction "P2[2]/PWM1[3]/CTS1/TRACEDATA[3]_73") (pintype "bidirectional"))
    )
    (net (code "84") (name "/TX_0") (class "Default")
      (node (ref "IC7") (pin "5") (pinfunction "RXD_5") (pintype "input"))
      (node (ref "LPC1769") (pin "98") (pinfunction "P0[2]/TXD0/AD0[7]_98") (pintype "bidirectional"))
    )
    (net (code "85") (name "/USBVCC") (class "Default")
      (node (ref "F1") (pin "1") (pinfunction "1_1") (pintype "passive"))
      (node (ref "T1") (pin "1") (pinfunction "D_1") (pintype "passive"))
    )
    (net (code "86") (name "/USB_N") (class "Default")
      (node (ref "C2") (pin "1") (pinfunction "1_1") (pintype "passive"))
      (node (ref "LPC1769") (pin "30") (pinfunction "P0[30]/USB_D-_30") (pintype "bidirectional"))
      (node (ref "R2") (pin "2") (pinfunction "2_2") (pintype "passive"))
    )
    (net (code "87") (name "/USB_P") (class "Default")
      (node (ref "C1") (pin "1") (pinfunction "1_1") (pintype "passive"))
      (node (ref "LPC1769") (pin "29") (pinfunction "P0[29]/USB_D+_29") (pintype "bidirectional"))
      (node (ref "R1") (pin "2") (pinfunction "2_2") (pintype "passive"))
      (node (ref "R73") (pin "1") (pinfunction "1_1") (pintype "passive"))
    )
    (net (code "88") (name "/X_MAX") (class "Default")
      (node (ref "LPC1769") (pin "39") (pinfunction "P1[25]/MC1A/MAT1[1]_39") (pintype "bidirectional"))
      (node (ref "X_MAX") (pin "3") (pinfunction "S_3") (pintype "passive"))
    )
    (net (code "89") (name "/X_MIN") (class "Default")
      (node (ref "LPC1769") (pin "38") (pinfunction "P1[24]/MCFB2/PWM1[5]/MOSI0_38") (pintype "bidirectional"))
      (node (ref "X_MIN") (pin "3") (pinfunction "S_3") (pintype "passive"))
    )
    (net (code "90") (name "/Y_MAX") (class "Default")
      (node (ref "LPC1769") (pin "43") (pinfunction "P1[27]/CLKOUT/USB_OVRCR/CAP0[1]_43") (pintype "bidirectional"))
      (node (ref "Y_MAX") (pin "3") (pinfunction "S_3") (pintype "passive"))
    )
    (net (code "91") (name "/Y_MIN") (class "Default")
      (node (ref "LPC1769") (pin "40") (pinfunction "P1[26]/MC1B/PWM1[6]/CAP0[0]_40") (pintype "bidirectional"))
      (node (ref "Y_MIN") (pin "3") (pinfunction "S_3") (pintype "passive"))
    )
    (net (code "92") (name "/Z_MAX") (class "Default")
      (node (ref "LPC1769") (pin "45") (pinfunction "P1[29]/MC2B/PCAP1[1]/MAT0[1]_45") (pintype "bidirectional"))
      (node (ref "Z_MAX") (pin "3") (pinfunction "S_3") (pintype "passive"))
    )
    (net (code "93") (name "/Z_MIN") (class "Default")
      (node (ref "LPC1769") (pin "44") (pinfunction "P1[28]/MC2A/PCAP1[0]/MAT0[0]_44") (pintype "bidirectional"))
      (node (ref "Z_MIN") (pin "3") (pinfunction "S_3") (pintype "passive"))
    )
    (net (code "94") (name "5V") (class "Default")
      (node (ref "C15") (pin "1") (pinfunction "1_1") (pintype "passive"))
      (node (ref "C76") (pin "+") (pinfunction "+_+") (pintype "passive"))
      (node (ref "C83") (pin "1") (pinfunction "1_1") (pintype "passive"))
      (node (ref "C84") (pin "1") (pinfunction "1_1") (pintype "passive"))
      (node (ref "C85") (pin "1") (pinfunction "1_1") (pintype "passive"))
      (node (ref "C86") (pin "1") (pinfunction "1_1") (pintype "passive"))
      (node (ref "END_STOP_V") (pin "1") (pinfunction "1_1") (pintype "passive"))
      (node (ref "FET_DRV1") (pin "6") (pinfunction "P$1_6") (pintype "bidirectional"))
      (node (ref "FET_DRV2") (pin "6") (pinfunction "P$1_6") (pintype "bidirectional"))
      (node (ref "IC10") (pin "3") (pinfunction "IN_3") (pintype "input"))
      (node (ref "IC8") (pin "4") (pinfunction "FB_4") (pintype "passive"))
      (node (ref "IC9") (pin "8") (pinfunction "V+_8") (pintype "power_in"))
      (node (ref "L4") (pin "2") (pinfunction "2_2") (pintype "passive"))
      (node (ref "PANEL") (pin "1") (pinfunction "KL_1") (pintype "passive"))
      (node (ref "R82") (pin "1") (pinfunction "1_1") (pintype "passive"))
      (node (ref "T1") (pin "2") (pinfunction "S_2") (pintype "passive"))
    )
    (net (code "95") (name "GND") (class "Default")
      (node (ref "+5V") (pin "C") (pinfunction "C_C") (pintype "passive"))
      (node (ref "3V3") (pin "C") (pinfunction "C_C") (pintype "passive"))
      (node (ref "AD5206") (pin "13") (pinfunction "B3_13") (pintype "bidirectional"))
      (node (ref "AD5206") (pin "16") (pinfunction "B1_16") (pintype "bidirectional"))
      (node (ref "AD5206") (pin "21") (pinfunction "B2_21") (pintype "bidirectional"))
      (node (ref "AD5206") (pin "24") (pinfunction "B4_24") (pintype "bidirectional"))
      (node (ref "AD5206") (pin "3") (pinfunction "B6_3") (pintype "bidirectional"))
      (node (ref "AD5206") (pin "4") (pinfunction "GND_4") (pintype "bidirectional"))
      (node (ref "AD5206") (pin "9") (pinfunction "VSS_9") (pintype "bidirectional"))
      (node (ref "C1") (pin "2") (pinfunction "2_2") (pintype "passive"))
      (node (ref "C10") (pin "2") (pinfunction "2_2") (pintype "passive"))
      (node (ref "C11") (pin "C") (pinfunction "-_C") (pintype "passive"))
      (node (ref "C12") (pin "2") (pinfunction "2_2") (pintype "passive"))
      (node (ref "C13") (pin "2") (pinfunction "2_2") (pintype "passive"))
      (node (ref "C14") (pin "C") (pinfunction "-_C") (pintype "passive"))
      (node (ref "C15") (pin "2") (pinfunction "2_2") (pintype "passive"))
      (node (ref "C16") (pin "2") (pinfunction "2_2") (pintype "passive"))
      (node (ref "C17") (pin "2") (pinfunction "2_2") (pintype "passive"))
      (node (ref "C19") (pin "1") (pinfunction "1_1") (pintype "passive"))
      (node (ref "C2") (pin "2") (pinfunction "2_2") (pintype "passive"))
      (node (ref "C21") (pin "1") (pinfunction "1_1") (pintype "passive"))
      (node (ref "C22") (pin "1") (pinfunction "1_1") (pintype "passive"))
      (node (ref "C23") (pin "-") (pinfunction "-_-") (pintype "passive"))
      (node (ref "C24") (pin "2") (pinfunction "2_2") (pintype "passive"))
      (node (ref "C25") (pin "1") (pinfunction "1_1") (pintype "passive"))
      (node (ref "C26") (pin "1") (pinfunction "1_1") (pintype "passive"))
      (node (ref "C27") (pin "1") (pinfunction "1_1") (pintype "passive"))
      (node (ref "C29") (pin "1") (pinfunction "1_1") (pintype "passive"))
      (node (ref "C3") (pin "2") (pinfunction "2_2") (pintype "passive"))
      (node (ref "C31") (pin "1") (pinfunction "1_1") (pintype "passive"))
      (node (ref "C32") (pin "1") (pinfunction "1_1") (pintype "passive"))
      (node (ref "C33") (pin "-") (pinfunction "-_-") (pintype "passive"))
      (node (ref "C34") (pin "2") (pinfunction "2_2") (pintype "passive"))
      (node (ref "C36") (pin "1") (pinfunction "1_1") (pintype "passive"))
      (node (ref "C38") (pin "1") (pinfunction "1_1") (pintype "passive"))
      (node (ref "C39") (pin "1") (pinfunction "1_1") (pintype "passive"))
      (node (ref "C4") (pin "2") (pinfunction "2_2") (pintype "passive"))
      (node (ref "C40") (pin "-") (pinfunction "-_-") (pintype "passive"))
      (node (ref "C41") (pin "2") (pinfunction "2_2") (pintype "passive"))
      (node (ref "C43") (pin "1") (pinfunction "1_1") (pintype "passive"))
      (node (ref "C45") (pin "1") (pinfunction "1_1") (pintype "passive"))
      (node (ref "C46") (pin "1") (pinfunction "1_1") (pintype "passive"))
      (node (ref "C47") (pin "-") (pinfunction "-_-") (pintype "passive"))
      (node (ref "C48") (pin "2") (pinfunction "2_2") (pintype "passive"))
      (node (ref "C5") (pin "2") (pinfunction "2_2") (pintype "passive"))
      (node (ref "C50") (pin "1") (pinfunction "1_1") (pintype "passive"))
      (node (ref "C52") (pin "1") (pinfunction "1_1") (pintype "passive"))
      (node (ref "C53") (pin "1") (pinfunction "1_1") (pintype "passive"))
      (node (ref "C54") (pin "-") (pinfunction "-_-") (pintype "passive"))
      (node (ref "C55") (pin "1") (pinfunction "1_1") (pintype "passive"))
      (node (ref "C56") (pin "C") (pinfunction "-_C") (pintype "passive"))
      (node (ref "C57") (pin "2") (pinfunction "2_2") (pintype "passive"))
      (node (ref "C58") (pin "2") (pinfunction "2_2") (pintype "passive"))
      (node (ref "C59") (pin "2") (pinfunction "2_2") (pintype "passive"))
      (node (ref "C6") (pin "2") (pinfunction "2_2") (pintype "passive"))
      (node (ref "C60") (pin "C") (pinfunction "-_C") (pintype "passive"))
      (node (ref "C61") (pin "C") (pinfunction "-_C") (pintype "passive"))
      (node (ref "C62") (pin "2") (pinfunction "2_2") (pintype "passive"))
      (node (ref "C63") (pin "2") (pinfunction "2_2") (pintype "passive"))
      (node (ref "C64") (pin "2") (pinfunction "2_2") (pintype "passive"))
      (node (ref "C65") (pin "2") (pinfunction "2_2") (pintype "passive"))
      (node (ref "C66") (pin "2") (pinfunction "2_2") (pintype "passive"))
      (node (ref "C67") (pin "2") (pinfunction "2_2") (pintype "passive"))
      (node (ref "C68") (pin "2") (pinfunction "2_2") (pintype "passive"))
      (node (ref "C69") (pin "2") (pinfunction "2_2") (pintype "passive"))
      (node (ref "C7") (pin "2") (pinfunction "2_2") (pintype "passive"))
      (node (ref "C70") (pin "2") (pinfunction "2_2") (pintype "passive"))
      (node (ref "C71") (pin "2") (pinfunction "2_2") (pintype "passive"))
      (node (ref "C72") (pin "1") (pinfunction "1_1") (pintype "passive"))
      (node (ref "C73") (pin "C") (pinfunction "-_C") (pintype "passive"))
      (node (ref "C74") (pin "-") (pinfunction "-_-") (pintype "passive"))
      (node (ref "C75") (pin "2") (pinfunction "2_2") (pintype "passive"))
      (node (ref "C76") (pin "-") (pinfunction "-_-") (pintype "passive"))
      (node (ref "C78") (pin "-") (pinfunction "-_-") (pintype "passive"))
      (node (ref "C79") (pin "2") (pinfunction "2_2") (pintype "passive"))
      (node (ref "C8") (pin "2") (pinfunction "2_2") (pintype "passive"))
      (node (ref "C82") (pin "2") (pinfunction "2_2") (pintype "passive"))
      (node (ref "C83") (pin "2") (pinfunction "2_2") (pintype "passive"))
      (node (ref "C84") (pin "2") (pinfunction "2_2") (pintype "passive"))
      (node (ref "C85") (pin "2") (pinfunction "2_2") (pintype "passive"))
      (node (ref "C86") (pin "2") (pinfunction "2_2") (pintype "passive"))
      (node (ref "C9") (pin "2") (pinfunction "2_2") (pintype "passive"))
      (node (ref "D1") (pin "A") (pinfunction "A_A") (pintype "passive"))
      (node (ref "D2") (pin "A") (pinfunction "A_A") (pintype "passive"))
      (node (ref "D3") (pin "A") (pinfunction "A_A") (pintype "passive"))
      (node (ref "E0_FET") (pin "3") (pinfunction "S_3") (pintype "passive"))
      (node (ref "E1_FET") (pin "3") (pinfunction "S_3") (pintype "passive"))
      (node (ref "FB3") (pin "1") (pinfunction "P$1_1") (pintype "passive"))
      (node (ref "FET_DRV1") (pin "3") (pinfunction "P$2_3") (pintype "bidirectional"))
      (node (ref "FET_DRV2") (pin "3") (pinfunction "P$2_3") (pintype "bidirectional"))
      (node (ref "HOTBET_FET") (pin "3") (pinfunction "S_3") (pintype "passive"))
      (node (ref "IC10") (pin "1") (pinfunction "GND_1") (pintype "input"))
      (node (ref "IC2") (pin "18") (pinfunction "GND_18") (pintype "power_in"))
      (node (ref "IC2") (pin "3") (pinfunction "GND_3") (pintype "power_in"))
      (node (ref "IC2") (pin "EXP") (pinfunction "EXP_EXP") (pintype "passive"))
      (node (ref "IC3") (pin "18") (pinfunction "GND_18") (pintype "power_in"))
      (node (ref "IC3") (pin "3") (pinfunction "GND_3") (pintype "power_in"))
      (node (ref "IC3") (pin "EXP") (pinfunction "EXP_EXP") (pintype "passive"))
      (node (ref "IC4") (pin "18") (pinfunction "GND_18") (pintype "power_in"))
      (node (ref "IC4") (pin "3") (pinfunction "GND_3") (pintype "power_in"))
      (node (ref "IC4") (pin "EXP") (pinfunction "EXP_EXP") (pintype "passive"))
      (node (ref "IC5") (pin "18") (pinfunction "GND_18") (pintype "power_in"))
      (node (ref "IC5") (pin "3") (pinfunction "GND_3") (pintype "power_in"))
      (node (ref "IC5") (pin "EXP") (pinfunction "EXP_EXP") (pintype "passive"))
      (node (ref "IC6") (pin "18") (pinfunction "GND_18") (pintype "power_in"))
      (node (ref "IC6") (pin "3") (pinfunction "GND_3") (pintype "power_in"))
      (node (ref "IC6") (pin "EXP") (pinfunction "EXP_EXP") (pintype "passive"))
      (node (ref "IC7") (pin "18") (pinfunction "GND18_18") (pintype "power_in"))
      (node (ref "IC7") (pin "21") (pinfunction "GND21_21") (pintype "power_in"))
      (node (ref "IC7") (pin "25") (pinfunction "AGND_25") (pintype "power_in"))
      (node (ref "IC7") (pin "26") (pinfunction "TEST_26") (pintype "input"))
      (node (ref "IC7") (pin "7") (pinfunction "GND7_7") (pintype "power_in"))
      (node (ref "IC8") (pin "6") (pinfunction "GND_6") (pintype "input"))
      (node (ref "IC9") (pin "4") (pinfunction "V-_4") (pintype "power_in"))
      (node (ref "LPC1769") (pin "11") (pinfunction "VSSA_11") (pintype "power_in"))
      (node (ref "LPC1769") (pin "15") (pinfunction "VREFN_15") (pintype "power_in"))
      (node (ref "LPC1769") (pin "31") (pinfunction "VSS1_31") (pintype "power_in"))
      (node (ref "LPC1769") (pin "41") (pinfunction "VSS2_41") (pintype "power_in"))
      (node (ref "LPC1769") (pin "55") (pinfunction "VSS3_55") (pintype "power_in"))
      (node (ref "LPC1769") (pin "72") (pinfunction "VSS4_72") (pintype "power_in"))
      (node (ref "LPC1769") (pin "83") (pinfunction "VSS6_83") (pintype "power_in"))
      (node (ref "LPC1769") (pin "97") (pinfunction "VSS5_97") (pintype "power_in"))
      (node (ref "PANEL") (pin "2") (pinfunction "KL_2") (pintype "passive"))
      (node (ref "PLAY") (pin "3") (pinfunction "3_3") (pintype "passive"))
      (node (ref "PLAY") (pin "4") (pinfunction "4_4") (pintype "passive"))
      (node (ref "PROGRAM") (pin "3") (pinfunction "3_3") (pintype "passive"))
      (node (ref "PROGRAM") (pin "4") (pinfunction "4_4") (pintype "passive"))
      (node (ref "Q2") (pin "S") (pinfunction "S_S") (pintype "passive"))
      (node (ref "Q3") (pin "S") (pinfunction "S_S") (pintype "passive"))
      (node (ref "Q4") (pin "S") (pinfunction "S_S") (pintype "passive"))
      (node (ref "R11") (pin "1") (pinfunction "1_1") (pintype "passive"))
      (node (ref "R12") (pin "2") (pinfunction "2_2") (pintype "passive"))
      (node (ref "R13") (pin "2") (pinfunction "2_2") (pintype "passive"))
      (node (ref "R15") (pin "2") (pinfunction "2_2") (pintype "passive"))
      (node (ref "R16") (pin "1") (pinfunction "1_1") (pintype "passive"))
      (node (ref "R18") (pin "1") (pinfunction "1_1") (pintype "passive"))
      (node (ref "R20") (pin "1") (pinfunction "1_1") (pintype "passive"))
      (node (ref "R28") (pin "1") (pinfunction "1_1") (pintype "passive"))
      (node (ref "R29") (pin "2") (pinfunction "2_2") (pintype "passive"))
      (node (ref "R30") (pin "2") (pinfunction "2_2") (pintype "passive"))
      (node (ref "R32") (pin "2") (pinfunction "2_2") (pintype "passive"))
      (node (ref "R36") (pin "1") (pinfunction "1_1") (pintype "passive"))
      (node (ref "R37") (pin "2") (pinfunction "2_2") (pintype "passive"))
      (node (ref "R38") (pin "2") (pinfunction "2_2") (pintype "passive"))
      (node (ref "R40") (pin "2") (pinfunction "2_2") (pintype "passive"))
      (node (ref "R44") (pin "1") (pinfunction "1_1") (pintype "passive"))
      (node (ref "R45") (pin "2") (pinfunction "2_2") (pintype "passive"))
      (node (ref "R46") (pin "2") (pinfunction "2_2") (pintype "passive"))
      (node (ref "R48") (pin "2") (pinfunction "2_2") (pintype "passive"))
      (node (ref "R52") (pin "1") (pinfunction "1_1") (pintype "passive"))
      (node (ref "R53") (pin "2") (pinfunction "2_2") (pintype "passive"))
      (node (ref "R54") (pin "2") (pinfunction "2_2") (pintype "passive"))
      (node (ref "R56") (pin "2") (pinfunction "2_2") (pintype "passive"))
      (node (ref "R63") (pin "2") (pinfunction "2_2") (pintype "passive"))
      (node (ref "R68") (pin "2") (pinfunction "2_2") (pintype "passive"))
      (node (ref "R69") (pin "2") (pinfunction "2_2") (pintype "passive"))
      (node (ref "R77") (pin "2") (pinfunction "2_2") (pintype "passive"))
      (node (ref "R79") (pin "2") (pinfunction "2_2") (pintype "passive"))
      (node (ref "R81") (pin "2") (pinfunction "2_2") (pintype "passive"))
      (node (ref "R89") (pin "2") (pinfunction "2_2") (pintype "passive"))
      (node (ref "R91") (pin "2") (pinfunction "2_2") (pintype "passive"))
      (node (ref "RESET") (pin "3") (pinfunction "3_3") (pintype "passive"))
      (node (ref "RESET") (pin "4") (pinfunction "4_4") (pintype "passive"))
      (node (ref "RJ1") (pin "CHS1") (pinfunction "CHS1_CHS1") (pintype "bidirectional"))
      (node (ref "RJ1") (pin "CHS2") (pinfunction "CHS2_CHS2") (pintype "bidirectional"))
      (node (ref "RJ1") (pin "GND") (pinfunction "GND_GND") (pintype "bidirectional"))
      (node (ref "RJ1") (pin "NC") (pinfunction "NC_NC") (pintype "bidirectional"))
      (node (ref "T_E0") (pin "1") (pinfunction "S_1") (pintype "passive"))
      (node (ref "T_E1") (pin "1") (pinfunction "S_1") (pintype "passive"))
      (node (ref "T_HB") (pin "1") (pinfunction "S_1") (pintype "passive"))
      (node (ref "U$1") (pin "GND") (pinfunction "GND_GND") (pintype "bidirectional"))
      (node (ref "U$3") (pin "GND1") (pinfunction "GND_GND1") (pintype "power_in"))
      (node (ref "U$3") (pin "GND2") (pinfunction "GND_GND2") (pintype "power_in"))
      (node (ref "U$7") (pin "GND") (pinfunction "GND_GND") (pintype "bidirectional"))
      (node (ref "U$7") (pin "MTN1") (pinfunction "MTN2_MTN1") (pintype "bidirectional"))
      (node (ref "U$7") (pin "MTN2") (pinfunction "MTN3_MTN2") (pintype "bidirectional"))
      (node (ref "U$7") (pin "MTN3") (pinfunction "MTN1_MTN3") (pintype "bidirectional"))
      (node (ref "U$7") (pin "MTN4") (pinfunction "MTN4_MTN4") (pintype "bidirectional"))
      (node (ref "U$8") (pin "GND1") (pinfunction "GND_GND1") (pintype "power_in"))
      (node (ref "U$8") (pin "GND2") (pinfunction "GND_GND2") (pintype "power_in"))
      (node (ref "U2") (pin "6") (pinfunction "GND_6") (pintype "bidirectional"))
      (node (ref "U2") (pin "GND1") (pinfunction "SHIELD_GND1") (pintype "bidirectional"))
      (node (ref "U2") (pin "GND3") (pinfunction "SHIELD_GND3") (pintype "bidirectional"))
      (node (ref "U3") (pin "THERM") (pinfunction "GND_THERM") (pintype "bidirectional"))
      (node (ref "U4") (pin "3") (pinfunction "GND_3") (pintype "power_in"))
      (node (ref "V_HEAT") (pin "1") (pinfunction "KL_1") (pintype "passive"))
      (node (ref "V_MOT") (pin "1") (pinfunction "KL_1") (pintype "passive"))
      (node (ref "X_MAX") (pin "1") (pinfunction "S_1") (pintype "passive"))
      (node (ref "X_MIN") (pin "1") (pinfunction "S_1") (pintype "passive"))
      (node (ref "Y_MAX") (pin "1") (pinfunction "S_1") (pintype "passive"))
      (node (ref "Y_MIN") (pin "1") (pinfunction "S_1") (pintype "passive"))
      (node (ref "Z_MAX") (pin "1") (pinfunction "S_1") (pintype "passive"))
      (node (ref "Z_MIN") (pin "1") (pinfunction "S_1") (pintype "passive"))
    )
    (net (code "96") (name "Net-(+5V-PadA)") (class "Default")
      (node (ref "+5V") (pin "A") (pinfunction "A_A") (pintype "passive"))
      (node (ref "R82") (pin "2") (pinfunction "2_2") (pintype "passive"))
    )
    (net (code "97") (name "Net-(3V3-PadA)") (class "Default")
      (node (ref "3V3") (pin "A") (pinfunction "A_A") (pintype "passive"))
      (node (ref "R4") (pin "2") (pinfunction "2_2") (pintype "passive"))
    )
    (net (code "98") (name "Net-(AD5206-A1)") (class "Default")
      (node (ref "AD5206") (pin "1") (pinfunction "A6_1") (pintype "bidirectional"))
      (node (ref "AD5206") (pin "15") (pinfunction "A3_15") (pintype "bidirectional"))
      (node (ref "AD5206") (pin "18") (pinfunction "A1_18") (pintype "bidirectional"))
      (node (ref "AD5206") (pin "19") (pinfunction "A2_19") (pintype "bidirectional"))
      (node (ref "AD5206") (pin "22") (pinfunction "A4_22") (pintype "bidirectional"))
      (node (ref "R83") (pin "1") (pinfunction "1_1") (pintype "passive"))
    )
    (net (code "99") (name "Net-(C56-+)") (class "Default")
      (node (ref "C56") (pin "A") (pinfunction "+_A") (pintype "passive"))
      (node (ref "C57") (pin "1") (pinfunction "1_1") (pintype "passive"))
      (node (ref "C58") (pin "1") (pinfunction "1_1") (pintype "passive"))
      (node (ref "FB1") (pin "2") (pinfunction "P$2_2") (pintype "passive"))
      (node (ref "U3") (pin "1") (pinfunction "VDD2A_1") (pintype "bidirectional"))
      (node (ref "U3") (pin "19") (pinfunction "VDD1A_19") (pintype "bidirectional"))
    )
    (net (code "100") (name "Net-(C60-+)") (class "Default")
      (node (ref "C60") (pin "A") (pinfunction "+_A") (pintype "passive"))
      (node (ref "C62") (pin "1") (pinfunction "1_1") (pintype "passive"))
      (node (ref "U3") (pin "6") (pinfunction "VDDCR_6") (pintype "bidirectional"))
    )
    (net (code "101") (name "Net-(C73-+)") (class "Default")
      (node (ref "C72") (pin "2") (pinfunction "2_2") (pintype "passive"))
      (node (ref "C73") (pin "A") (pinfunction "+_A") (pintype "passive"))
      (node (ref "F2") (pin "1") (pinfunction "1_1") (pintype "passive"))
      (node (ref "IC7") (pin "20") (pinfunction "VCC_20") (pintype "power_in"))
    )
    (net (code "102") (name "Net-(E0B-KL)") (class "Default")
      (node (ref "E0") (pin "2") (pinfunction "KL_2") (pintype "passive"))
      (node (ref "E0_FET") (pin "4") (pinfunction "D_4") (pintype "passive"))
      (node (ref "LED6") (pin "C") (pinfunction "C_C") (pintype "passive"))
    )
    (net (code "103") (name "Net-(E0_AXISA-S)") (class "Default")
      (node (ref "E0_AXIS") (pin "1") (pinfunction "S_1") (pintype "passive"))
      (node (ref "IC2") (pin "21") (pinfunction "OUT1B_21") (pintype "output"))
    )
    (net (code "104") (name "Net-(E0_AXISB-S)") (class "Default")
      (node (ref "E0_AXIS") (pin "2") (pinfunction "S_2") (pintype "passive"))
      (node (ref "IC2") (pin "24") (pinfunction "OUT1A_24") (pintype "output"))
    )
    (net (code "105") (name "Net-(E0_AXISC-S)") (class "Default")
      (node (ref "E0_AXIS") (pin "3") (pinfunction "S_3") (pintype "passive"))
      (node (ref "IC2") (pin "26") (pinfunction "OUT2A_26") (pintype "output"))
    )
    (net (code "106") (name "Net-(E0_AXISD-S)") (class "Default")
      (node (ref "E0_AXIS") (pin "4") (pinfunction "S_4") (pintype "passive"))
      (node (ref "IC2") (pin "1") (pinfunction "OUT2B_1") (pintype "output"))
    )
    (net (code "107") (name "Net-(E0_FET-G)") (class "Default")
      (node (ref "E0_FET") (pin "1") (pinfunction "G_1") (pintype "passive"))
      (node (ref "R76") (pin "1") (pinfunction "1_1") (pintype "passive"))
    )
    (net (code "108") (name "Net-(E1B-KL)") (class "Default")
      (node (ref "E1") (pin "2") (pinfunction "KL_2") (pintype "passive"))
      (node (ref "E1_FET") (pin "4") (pinfunction "D_4") (pintype "passive"))
      (node (ref "LED7") (pin "C") (pinfunction "C_C") (pintype "passive"))
    )
    (net (code "109") (name "Net-(E1_AXISA-S)") (class "Default")
      (node (ref "E1_AXIS") (pin "1") (pinfunction "S_1") (pintype "passive"))
      (node (ref "IC6") (pin "21") (pinfunction "OUT1B_21") (pintype "output"))
    )
    (net (code "110") (name "Net-(E1_AXISB-S)") (class "Default")
      (node (ref "E1_AXIS") (pin "2") (pinfunction "S_2") (pintype "passive"))
      (node (ref "IC6") (pin "24") (pinfunction "OUT1A_24") (pintype "output"))
    )
    (net (code "111") (name "Net-(E1_AXISC-S)") (class "Default")
      (node (ref "E1_AXIS") (pin "3") (pinfunction "S_3") (pintype "passive"))
      (node (ref "IC6") (pin "26") (pinfunction "OUT2A_26") (pintype "output"))
    )
    (net (code "112") (name "Net-(E1_AXISD-S)") (class "Default")
      (node (ref "E1_AXIS") (pin "4") (pinfunction "S_4") (pintype "passive"))
      (node (ref "IC6") (pin "1") (pinfunction "OUT2B_1") (pintype "output"))
    )
    (net (code "113") (name "Net-(E1_FET-G)") (class "Default")
      (node (ref "E1_FET") (pin "1") (pinfunction "G_1") (pintype "passive"))
      (node (ref "R78") (pin "1") (pinfunction "1_1") (pintype "passive"))
    )
    (net (code "114") (name "Net-(F1-Pad2)") (class "Default")
      (node (ref "F1") (pin "2") (pinfunction "2_2") (pintype "passive"))
      (node (ref "U$1") (pin "VBUS") (pinfunction "VBUS_VBUS") (pintype "bidirectional"))
    )
    (net (code "115") (name "Net-(F2-Pad2)") (class "Default")
      (node (ref "F2") (pin "2") (pinfunction "2_2") (pintype "passive"))
      (node (ref "U$7") (pin "VBUS") (pinfunction "VBUS_VBUS") (pintype "bidirectional"))
    )
    (net (code "116") (name "Net-(FAN1A-S)") (class "Default")
      (node (ref "FAN1") (pin "1") (pinfunction "S_1") (pintype "passive"))
      (node (ref "LED2") (pin "C") (pinfunction "C_C") (pintype "passive"))
      (node (ref "Q2") (pin "D") (pinfunction "D_D") (pintype "passive"))
    )
    (net (code "117") (name "Net-(FAN2A-S)") (class "Default")
      (node (ref "FAN2") (pin "1") (pinfunction "S_1") (pintype "passive"))
      (node (ref "LED3") (pin "C") (pinfunction "C_C") (pintype "passive"))
      (node (ref "Q3") (pin "D") (pinfunction "D_D") (pintype "passive"))
    )
    (net (code "118") (name "Net-(FAN3A-S)") (class "Default")
      (node (ref "FAN3") (pin "1") (pinfunction "S_1") (pintype "passive"))
      (node (ref "LED4") (pin "C") (pinfunction "C_C") (pintype "passive"))
      (node (ref "Q4") (pin "D") (pinfunction "D_D") (pintype "passive"))
    )
    (net (code "119") (name "Net-(FB2-P$2)") (class "Default")
      (node (ref "C82") (pin "1") (pinfunction "1_1") (pintype "passive"))
      (node (ref "FB2") (pin "2") (pinfunction "P$2_2") (pintype "passive"))
      (node (ref "RJ1") (pin "CT") (pinfunction "CT_CT") (pintype "bidirectional"))
      (node (ref "RJ1") (pin "CT2") (pinfunction "CT2_CT2") (pintype "bidirectional"))
    )
    (net (code "120") (name "Net-(FB3-P$2)") (class "Default")
      (node (ref "FB3") (pin "2") (pinfunction "P$2_2") (pintype "passive"))
      (node (ref "R97") (pin "2") (pinfunction "2_2") (pintype "passive"))
      (node (ref "R98") (pin "2") (pinfunction "2_2") (pintype "passive"))
      (node (ref "U$1") (pin "S1") (pinfunction "P$1_S1") (pintype "bidirectional"))
      (node (ref "U$1") (pin "S2") (pinfunction "P$2_S2") (pintype "bidirectional"))
    )
    (net (code "121") (name "Net-(FET_DRV1A-P$2)") (class "Default")
      (node (ref "FET_DRV1") (pin "7") (pinfunction "P$2_7") (pintype "bidirectional"))
      (node (ref "R76") (pin "2") (pinfunction "2_2") (pintype "passive"))
    )
    (net (code "122") (name "Net-(FET_DRV1B-P$2)") (class "Default")
      (node (ref "FET_DRV1") (pin "5") (pinfunction "P$2_5") (pintype "bidirectional"))
      (node (ref "R78") (pin "2") (pinfunction "2_2") (pintype "passive"))
    )
    (net (code "123") (name "Net-(FET_DRV2A-P$2)") (class "Default")
      (node (ref "FET_DRV2") (pin "7") (pinfunction "P$2_7") (pintype "bidirectional"))
      (node (ref "R80") (pin "2") (pinfunction "2_2") (pintype "passive"))
    )
    (net (code "124") (name "Net-(HBB-KL)") (class "Default")
      (node (ref "HB") (pin "2") (pinfunction "KL_2") (pintype "passive"))
      (node (ref "HOTBET_FET") (pin "4") (pinfunction "D_4") (pintype "passive"))
      (node (ref "LED8") (pin "C") (pinfunction "C_C") (pintype "passive"))
    )
    (net (code "125") (name "Net-(HOTBET_FET-G)") (class "Default")
      (node (ref "HOTBET_FET") (pin "1") (pinfunction "G_1") (pintype "passive"))
      (node (ref "R80") (pin "1") (pinfunction "1_1") (pintype "passive"))
    )
    (net (code "126") (name "Net-(IC2-CP1)") (class "Default")
      (node (ref "C18") (pin "1") (pinfunction "1_1") (pintype "passive"))
      (node (ref "IC2") (pin "4") (pinfunction "CP1_4") (pintype "passive"))
    )
    (net (code "127") (name "Net-(IC2-CP2)") (class "Default")
      (node (ref "C18") (pin "2") (pinfunction "2_2") (pintype "passive"))
      (node (ref "IC2") (pin "5") (pinfunction "CP2_5") (pintype "passive"))
    )
    (net (code "128") (name "Net-(IC2-MS1)") (class "Default")
      (node (ref "IC2") (pin "9") (pinfunction "MS1_9") (pintype "input"))
      (node (ref "MS1") (pin "2") (pinfunction "2_2") (pintype "passive"))
      (node (ref "R15") (pin "1") (pinfunction "1_1") (pintype "passive"))
    )
    (net (code "129") (name "Net-(IC2-MS2)") (class "Default")
      (node (ref "IC2") (pin "10") (pinfunction "MS2_10") (pintype "input"))
      (node (ref "MS2") (pin "2") (pinfunction "2_2") (pintype "passive"))
    )
    (net (code "130") (name "Net-(IC2-MS3)") (class "Default")
      (node (ref "IC2") (pin "11") (pinfunction "MS3_11") (pintype "input"))
      (node (ref "MS3") (pin "2") (pinfunction "2_2") (pintype "passive"))
    )
    (net (code "131") (name "Net-(IC2-RESET)") (class "Default")
      (node (ref "IC2") (pin "12") (pinfunction "RESET_12") (pintype "input"))
      (node (ref "R8") (pin "2") (pinfunction "2_2") (pintype "passive"))
    )
    (net (code "132") (name "Net-(IC2-ROSC)") (class "Default")
      (node (ref "IC2") (pin "13") (pinfunction "ROSC_13") (pintype "input"))
      (node (ref "R10") (pin "2") (pinfunction "2_2") (pintype "passive"))
      (node (ref "R11") (pin "2") (pinfunction "2_2") (pintype "passive"))
    )
    (net (code "133") (name "Net-(IC2-SENSE1)") (class "Default")
      (node (ref "IC2") (pin "23") (pinfunction "SENSE1_23") (pintype "input"))
      (node (ref "R13") (pin "1") (pinfunction "1_1") (pintype "passive"))
    )
    (net (code "134") (name "Net-(IC2-SENSE2)") (class "Default")
      (node (ref "IC2") (pin "27") (pinfunction "SENSE2_27") (pintype "input"))
      (node (ref "R12") (pin "1") (pinfunction "1_1") (pintype "passive"))
    )
    (net (code "135") (name "Net-(IC2-SLEEP)") (class "Default")
      (node (ref "IC2") (pin "14") (pinfunction "SLEEP_14") (pintype "input"))
      (node (ref "R9") (pin "2") (pinfunction "2_2") (pintype "passive"))
    )
    (net (code "136") (name "Net-(IC2-VCP)") (class "Default")
      (node (ref "C20") (pin "1") (pinfunction "1_1") (pintype "passive"))
      (node (ref "IC2") (pin "6") (pinfunction "VCP_6") (pintype "passive"))
    )
    (net (code "137") (name "Net-(IC2-VREG)") (class "Default")
      (node (ref "C16") (pin "1") (pinfunction "1_1") (pintype "passive"))
      (node (ref "IC2") (pin "8") (pinfunction "VREG_8") (pintype "passive"))
    )
    (net (code "138") (name "Net-(IC3-CP1)") (class "Default")
      (node (ref "C28") (pin "1") (pinfunction "1_1") (pintype "passive"))
      (node (ref "IC3") (pin "4") (pinfunction "CP1_4") (pintype "passive"))
    )
    (net (code "139") (name "Net-(IC3-CP2)") (class "Default")
      (node (ref "C28") (pin "2") (pinfunction "2_2") (pintype "passive"))
      (node (ref "IC3") (pin "5") (pinfunction "CP2_5") (pintype "passive"))
    )
    (net (code "140") (name "Net-(IC3-MS1)") (class "Default")
      (node (ref "IC3") (pin "9") (pinfunction "MS1_9") (pintype "input"))
      (node (ref "MS4") (pin "2") (pinfunction "2_2") (pintype "passive"))
      (node (ref "R32") (pin "1") (pinfunction "1_1") (pintype "passive"))
    )
    (net (code "141") (name "Net-(IC3-MS2)") (class "Default")
      (node (ref "IC3") (pin "10") (pinfunction "MS2_10") (pintype "input"))
      (node (ref "MS5") (pin "2") (pinfunction "2_2") (pintype "passive"))
    )
    (net (code "142") (name "Net-(IC3-MS3)") (class "Default")
      (node (ref "IC3") (pin "11") (pinfunction "MS3_11") (pintype "input"))
      (node (ref "MS6") (pin "2") (pinfunction "2_2") (pintype "passive"))
    )
    (net (code "143") (name "Net-(IC3-OUT1A)") (class "Default")
      (node (ref "IC3") (pin "24") (pinfunction "OUT1A_24") (pintype "output"))
      (node (ref "Z_AXIS") (pin "2") (pinfunction "S_2") (pintype "passive"))
    )
    (net (code "144") (name "Net-(IC3-OUT1B)") (class "Default")
      (node (ref "IC3") (pin "21") (pinfunction "OUT1B_21") (pintype "output"))
      (node (ref "Z_AXIS") (pin "1") (pinfunction "S_1") (pintype "passive"))
    )
    (net (code "145") (name "Net-(IC3-OUT2A)") (class "Default")
      (node (ref "IC3") (pin "26") (pinfunction "OUT2A_26") (pintype "output"))
      (node (ref "Z_AXIS") (pin "3") (pinfunction "S_3") (pintype "passive"))
    )
    (net (code "146") (name "Net-(IC3-OUT2B)") (class "Default")
      (node (ref "IC3") (pin "1") (pinfunction "OUT2B_1") (pintype "output"))
      (node (ref "Z_AXIS") (pin "4") (pinfunction "S_4") (pintype "passive"))
    )
    (net (code "147") (name "Net-(IC3-RESET)") (class "Default")
      (node (ref "IC3") (pin "12") (pinfunction "RESET_12") (pintype "input"))
      (node (ref "R25") (pin "2") (pinfunction "2_2") (pintype "passive"))
    )
    (net (code "148") (name "Net-(IC3-ROSC)") (class "Default")
      (node (ref "IC3") (pin "13") (pinfunction "ROSC_13") (pintype "input"))
      (node (ref "R27") (pin "2") (pinfunction "2_2") (pintype "passive"))
      (node (ref "R28") (pin "2") (pinfunction "2_2") (pintype "passive"))
    )
    (net (code "149") (name "Net-(IC3-SENSE1)") (class "Default")
      (node (ref "IC3") (pin "23") (pinfunction "SENSE1_23") (pintype "input"))
      (node (ref "R30") (pin "1") (pinfunction "1_1") (pintype "passive"))
    )
    (net (code "150") (name "Net-(IC3-SENSE2)") (class "Default")
      (node (ref "IC3") (pin "27") (pinfunction "SENSE2_27") (pintype "input"))
      (node (ref "R29") (pin "1") (pinfunction "1_1") (pintype "passive"))
    )
    (net (code "151") (name "Net-(IC3-SLEEP)") (class "Default")
      (node (ref "IC3") (pin "14") (pinfunction "SLEEP_14") (pintype "input"))
      (node (ref "R26") (pin "2") (pinfunction "2_2") (pintype "passive"))
    )
    (net (code "152") (name "Net-(IC3-VCP)") (class "Default")
      (node (ref "C30") (pin "1") (pinfunction "1_1") (pintype "passive"))
      (node (ref "IC3") (pin "6") (pinfunction "VCP_6") (pintype "passive"))
    )
    (net (code "153") (name "Net-(IC3-VREG)") (class "Default")
      (node (ref "C24") (pin "1") (pinfunction "1_1") (pintype "passive"))
      (node (ref "IC3") (pin "8") (pinfunction "VREG_8") (pintype "passive"))
    )
    (net (code "154") (name "Net-(IC4-CP1)") (class "Default")
      (node (ref "C35") (pin "1") (pinfunction "1_1") (pintype "passive"))
      (node (ref "IC4") (pin "4") (pinfunction "CP1_4") (pintype "passive"))
    )
    (net (code "155") (name "Net-(IC4-CP2)") (class "Default")
      (node (ref "C35") (pin "2") (pinfunction "2_2") (pintype "passive"))
      (node (ref "IC4") (pin "5") (pinfunction "CP2_5") (pintype "passive"))
    )
    (net (code "156") (name "Net-(IC4-MS1)") (class "Default")
      (node (ref "IC4") (pin "9") (pinfunction "MS1_9") (pintype "input"))
      (node (ref "MS7") (pin "2") (pinfunction "2_2") (pintype "passive"))
      (node (ref "R40") (pin "1") (pinfunction "1_1") (pintype "passive"))
    )
    (net (code "157") (name "Net-(IC4-MS2)") (class "Default")
      (node (ref "IC4") (pin "10") (pinfunction "MS2_10") (pintype "input"))
      (node (ref "MS8") (pin "2") (pinfunction "2_2") (pintype "passive"))
    )
    (net (code "158") (name "Net-(IC4-MS3)") (class "Default")
      (node (ref "IC4") (pin "11") (pinfunction "MS3_11") (pintype "input"))
      (node (ref "MS9") (pin "2") (pinfunction "2_2") (pintype "passive"))
    )
    (net (code "159") (name "Net-(IC4-OUT1A)") (class "Default")
      (node (ref "IC4") (pin "24") (pinfunction "OUT1A_24") (pintype "output"))
      (node (ref "Y_AXIS") (pin "2") (pinfunction "S_2") (pintype "passive"))
    )
    (net (code "160") (name "Net-(IC4-OUT1B)") (class "Default")
      (node (ref "IC4") (pin "21") (pinfunction "OUT1B_21") (pintype "output"))
      (node (ref "Y_AXIS") (pin "1") (pinfunction "S_1") (pintype "passive"))
    )
    (net (code "161") (name "Net-(IC4-OUT2A)") (class "Default")
      (node (ref "IC4") (pin "26") (pinfunction "OUT2A_26") (pintype "output"))
      (node (ref "Y_AXIS") (pin "3") (pinfunction "S_3") (pintype "passive"))
    )
    (net (code "162") (name "Net-(IC4-OUT2B)") (class "Default")
      (node (ref "IC4") (pin "1") (pinfunction "OUT2B_1") (pintype "output"))
      (node (ref "Y_AXIS") (pin "4") (pinfunction "S_4") (pintype "passive"))
    )
    (net (code "163") (name "Net-(IC4-RESET)") (class "Default")
      (node (ref "IC4") (pin "12") (pinfunction "RESET_12") (pintype "input"))
      (node (ref "R33") (pin "2") (pinfunction "2_2") (pintype "passive"))
    )
    (net (code "164") (name "Net-(IC4-ROSC)") (class "Default")
      (node (ref "IC4") (pin "13") (pinfunction "ROSC_13") (pintype "input"))
      (node (ref "R35") (pin "2") (pinfunction "2_2") (pintype "passive"))
      (node (ref "R36") (pin "2") (pinfunction "2_2") (pintype "passive"))
    )
    (net (code "165") (name "Net-(IC4-SENSE1)") (class "Default")
      (node (ref "IC4") (pin "23") (pinfunction "SENSE1_23") (pintype "input"))
      (node (ref "R38") (pin "1") (pinfunction "1_1") (pintype "passive"))
    )
    (net (code "166") (name "Net-(IC4-SENSE2)") (class "Default")
      (node (ref "IC4") (pin "27") (pinfunction "SENSE2_27") (pintype "input"))
      (node (ref "R37") (pin "1") (pinfunction "1_1") (pintype "passive"))
    )
    (net (code "167") (name "Net-(IC4-SLEEP)") (class "Default")
      (node (ref "IC4") (pin "14") (pinfunction "SLEEP_14") (pintype "input"))
      (node (ref "R34") (pin "2") (pinfunction "2_2") (pintype "passive"))
    )
    (net (code "168") (name "Net-(IC4-VCP)") (class "Default")
      (node (ref "C37") (pin "1") (pinfunction "1_1") (pintype "passive"))
      (node (ref "IC4") (pin "6") (pinfunction "VCP_6") (pintype "passive"))
    )
    (net (code "169") (name "Net-(IC4-VREG)") (class "Default")
      (node (ref "C34") (pin "1") (pinfunction "1_1") (pintype "passive"))
      (node (ref "IC4") (pin "8") (pinfunction "VREG_8") (pintype "passive"))
    )
    (net (code "170") (name "Net-(IC5-CP1)") (class "Default")
      (node (ref "C42") (pin "1") (pinfunction "1_1") (pintype "passive"))
      (node (ref "IC5") (pin "4") (pinfunction "CP1_4") (pintype "passive"))
    )
    (net (code "171") (name "Net-(IC5-CP2)") (class "Default")
      (node (ref "C42") (pin "2") (pinfunction "2_2") (pintype "passive"))
      (node (ref "IC5") (pin "5") (pinfunction "CP2_5") (pintype "passive"))
    )
    (net (code "172") (name "Net-(IC5-MS1)") (class "Default")
      (node (ref "IC5") (pin "9") (pinfunction "MS1_9") (pintype "input"))
      (node (ref "MS10") (pin "2") (pinfunction "2_2") (pintype "passive"))
      (node (ref "R48") (pin "1") (pinfunction "1_1") (pintype "passive"))
    )
    (net (code "173") (name "Net-(IC5-MS2)") (class "Default")
      (node (ref "IC5") (pin "10") (pinfunction "MS2_10") (pintype "input"))
      (node (ref "MS11") (pin "2") (pinfunction "2_2") (pintype "passive"))
    )
    (net (code "174") (name "Net-(IC5-MS3)") (class "Default")
      (node (ref "IC5") (pin "11") (pinfunction "MS3_11") (pintype "input"))
      (node (ref "MS12") (pin "2") (pinfunction "2_2") (pintype "passive"))
    )
    (net (code "175") (name "Net-(IC5-OUT1A)") (class "Default")
      (node (ref "IC5") (pin "24") (pinfunction "OUT1A_24") (pintype "output"))
      (node (ref "X_AXIS") (pin "2") (pinfunction "S_2") (pintype "passive"))
    )
    (net (code "176") (name "Net-(IC5-OUT1B)") (class "Default")
      (node (ref "IC5") (pin "21") (pinfunction "OUT1B_21") (pintype "output"))
      (node (ref "X_AXIS") (pin "1") (pinfunction "S_1") (pintype "passive"))
    )
    (net (code "177") (name "Net-(IC5-OUT2A)") (class "Default")
      (node (ref "IC5") (pin "26") (pinfunction "OUT2A_26") (pintype "output"))
      (node (ref "X_AXIS") (pin "3") (pinfunction "S_3") (pintype "passive"))
    )
    (net (code "178") (name "Net-(IC5-OUT2B)") (class "Default")
      (node (ref "IC5") (pin "1") (pinfunction "OUT2B_1") (pintype "output"))
      (node (ref "X_AXIS") (pin "4") (pinfunction "S_4") (pintype "passive"))
    )
    (net (code "179") (name "Net-(IC5-RESET)") (class "Default")
      (node (ref "IC5") (pin "12") (pinfunction "RESET_12") (pintype "input"))
      (node (ref "R41") (pin "2") (pinfunction "2_2") (pintype "passive"))
    )
    (net (code "180") (name "Net-(IC5-ROSC)") (class "Default")
      (node (ref "IC5") (pin "13") (pinfunction "ROSC_13") (pintype "input"))
      (node (ref "R43") (pin "2") (pinfunction "2_2") (pintype "passive"))
      (node (ref "R44") (pin "2") (pinfunction "2_2") (pintype "passive"))
    )
    (net (code "181") (name "Net-(IC5-SENSE1)") (class "Default")
      (node (ref "IC5") (pin "23") (pinfunction "SENSE1_23") (pintype "input"))
      (node (ref "R46") (pin "1") (pinfunction "1_1") (pintype "passive"))
    )
    (net (code "182") (name "Net-(IC5-SENSE2)") (class "Default")
      (node (ref "IC5") (pin "27") (pinfunction "SENSE2_27") (pintype "input"))
      (node (ref "R45") (pin "1") (pinfunction "1_1") (pintype "passive"))
    )
    (net (code "183") (name "Net-(IC5-SLEEP)") (class "Default")
      (node (ref "IC5") (pin "14") (pinfunction "SLEEP_14") (pintype "input"))
      (node (ref "R42") (pin "2") (pinfunction "2_2") (pintype "passive"))
    )
    (net (code "184") (name "Net-(IC5-VCP)") (class "Default")
      (node (ref "C44") (pin "1") (pinfunction "1_1") (pintype "passive"))
      (node (ref "IC5") (pin "6") (pinfunction "VCP_6") (pintype "passive"))
    )
    (net (code "185") (name "Net-(IC5-VREG)") (class "Default")
      (node (ref "C41") (pin "1") (pinfunction "1_1") (pintype "passive"))
      (node (ref "IC5") (pin "8") (pinfunction "VREG_8") (pintype "passive"))
    )
    (net (code "186") (name "Net-(IC6-CP1)") (class "Default")
      (node (ref "C49") (pin "1") (pinfunction "1_1") (pintype "passive"))
      (node (ref "IC6") (pin "4") (pinfunction "CP1_4") (pintype "passive"))
    )
    (net (code "187") (name "Net-(IC6-CP2)") (class "Default")
      (node (ref "C49") (pin "2") (pinfunction "2_2") (pintype "passive"))
      (node (ref "IC6") (pin "5") (pinfunction "CP2_5") (pintype "passive"))
    )
    (net (code "188") (name "Net-(IC6-MS1)") (class "Default")
      (node (ref "IC6") (pin "9") (pinfunction "MS1_9") (pintype "input"))
      (node (ref "MS13") (pin "2") (pinfunction "2_2") (pintype "passive"))
      (node (ref "R56") (pin "1") (pinfunction "1_1") (pintype "passive"))
    )
    (net (code "189") (name "Net-(IC6-MS2)") (class "Default")
      (node (ref "IC6") (pin "10") (pinfunction "MS2_10") (pintype "input"))
      (node (ref "MS14") (pin "2") (pinfunction "2_2") (pintype "passive"))
    )
    (net (code "190") (name "Net-(IC6-MS3)") (class "Default")
      (node (ref "IC6") (pin "11") (pinfunction "MS3_11") (pintype "input"))
      (node (ref "MS15") (pin "2") (pinfunction "2_2") (pintype "passive"))
    )
    (net (code "191") (name "Net-(IC6-RESET)") (class "Default")
      (node (ref "IC6") (pin "12") (pinfunction "RESET_12") (pintype "input"))
      (node (ref "R49") (pin "2") (pinfunction "2_2") (pintype "passive"))
    )
    (net (code "192") (name "Net-(IC6-ROSC)") (class "Default")
      (node (ref "IC6") (pin "13") (pinfunction "ROSC_13") (pintype "input"))
      (node (ref "R51") (pin "2") (pinfunction "2_2") (pintype "passive"))
      (node (ref "R52") (pin "2") (pinfunction "2_2") (pintype "passive"))
    )
    (net (code "193") (name "Net-(IC6-SENSE1)") (class "Default")
      (node (ref "IC6") (pin "23") (pinfunction "SENSE1_23") (pintype "input"))
      (node (ref "R54") (pin "1") (pinfunction "1_1") (pintype "passive"))
    )
    (net (code "194") (name "Net-(IC6-SENSE2)") (class "Default")
      (node (ref "IC6") (pin "27") (pinfunction "SENSE2_27") (pintype "input"))
      (node (ref "R53") (pin "1") (pinfunction "1_1") (pintype "passive"))
    )
    (net (code "195") (name "Net-(IC6-SLEEP)") (class "Default")
      (node (ref "IC6") (pin "14") (pinfunction "SLEEP_14") (pintype "input"))
      (node (ref "R50") (pin "2") (pinfunction "2_2") (pintype "passive"))
    )
    (net (code "196") (name "Net-(IC6-VCP)") (class "Default")
      (node (ref "C51") (pin "1") (pinfunction "1_1") (pintype "passive"))
      (node (ref "IC6") (pin "6") (pinfunction "VCP_6") (pintype "passive"))
    )
    (net (code "197") (name "Net-(IC6-VREG)") (class "Default")
      (node (ref "C48") (pin "1") (pinfunction "1_1") (pintype "passive"))
      (node (ref "IC6") (pin "8") (pinfunction "VREG_8") (pintype "passive"))
    )
    (net (code "198") (name "Net-(IC7-3V3OUT)") (class "Default")
      (node (ref "C55") (pin "2") (pinfunction "2_2") (pintype "passive"))
      (node (ref "IC7") (pin "17") (pinfunction "3V3OUT_17") (pintype "output"))
      (node (ref "IC7") (pin "4") (pinfunction "VCCIO_4") (pintype "power_in"))
    )
    (net (code "199") (name "Net-(IC7-RXLED)") (class "Default")
      (node (ref "IC7") (pin "22") (pinfunction "RXLED_22") (pintype "input"))
      (node (ref "RX") (pin "C") (pinfunction "C_C") (pintype "passive"))
    )
    (net (code "200") (name "Net-(IC7-TXLED)") (class "Default")
      (node (ref "IC7") (pin "23") (pinfunction "TXLED_23") (pintype "input"))
      (node (ref "TX") (pin "C") (pinfunction "C_C") (pintype "passive"))
    )
    (net (code "201") (name "Net-(IC7-USBDM)") (class "Default")
      (node (ref "IC7") (pin "16") (pinfunction "USBDM_16") (pintype "bidirectional"))
      (node (ref "U$7") (pin "D-") (pinfunction "D-_D-") (pintype "bidirectional"))
    )
    (net (code "202") (name "Net-(IC7-USBDP)") (class "Default")
      (node (ref "IC7") (pin "15") (pinfunction "USBDP_15") (pintype "bidirectional"))
      (node (ref "U$7") (pin "D+") (pinfunction "D+_D+") (pintype "bidirectional"))
    )
    (net (code "203") (name "Net-(IC8-CB)") (class "Default")
      (node (ref "C77") (pin "1") (pinfunction "1_1") (pintype "passive"))
      (node (ref "IC8") (pin "1") (pinfunction "CB_1") (pintype "passive"))
    )
    (net (code "204") (name "Net-(IC8-VSW)") (class "Default")
      (node (ref "C77") (pin "2") (pinfunction "2_2") (pintype "passive"))
      (node (ref "D1") (pin "C") (pinfunction "C_C") (pintype "passive"))
      (node (ref "IC8") (pin "8") (pinfunction "VSW_8") (pintype "passive"))
      (node (ref "L4") (pin "1") (pinfunction "1_1") (pintype "passive"))
    )
    (net (code "205") (name "Net-(IC9A-+IN)") (class "Default")
      (node (ref "IC9") (pin "3") (pinfunction "+IN_3") (pintype "input"))
      (node (ref "R90") (pin "1") (pinfunction "1_1") (pintype "passive"))
      (node (ref "R91") (pin "1") (pinfunction "1_1") (pintype "passive"))
    )
    (net (code "206") (name "Net-(IC9A-OUT)") (class "Default")
      (node (ref "IC9") (pin "1") (pinfunction "OUT_1") (pintype "output"))
      (node (ref "T1") (pin "3") (pinfunction "G_3") (pintype "passive"))
    )
    (net (code "207") (name "Net-(LED2-PadA)") (class "Default")
      (node (ref "LED2") (pin "A") (pinfunction "A_A") (pintype "passive"))
      (node (ref "R17") (pin "2") (pinfunction "2_2") (pintype "passive"))
    )
    (net (code "208") (name "Net-(LED3-PadA)") (class "Default")
      (node (ref "LED3") (pin "A") (pinfunction "A_A") (pintype "passive"))
      (node (ref "R19") (pin "2") (pinfunction "2_2") (pintype "passive"))
    )
    (net (code "209") (name "Net-(LED4-PadA)") (class "Default")
      (node (ref "LED4") (pin "A") (pinfunction "A_A") (pintype "passive"))
      (node (ref "R21") (pin "2") (pinfunction "2_2") (pintype "passive"))
    )
    (net (code "210") (name "Net-(LED6-PadA)") (class "Default")
      (node (ref "LED6") (pin "A") (pinfunction "A_A") (pintype "passive"))
      (node (ref "R94") (pin "2") (pinfunction "2_2") (pintype "passive"))
    )
    (net (code "211") (name "Net-(LED7-PadA)") (class "Default")
      (node (ref "LED7") (pin "A") (pinfunction "A_A") (pintype "passive"))
      (node (ref "R95") (pin "2") (pinfunction "2_2") (pintype "passive"))
    )
    (net (code "212") (name "Net-(LED8-PadA)") (class "Default")
      (node (ref "LED8") (pin "A") (pinfunction "A_A") (pintype "passive"))
      (node (ref "R96") (pin "2") (pinfunction "2_2") (pintype "passive"))
    )
    (net (code "213") (name "Net-(LPC1769-VDDA)") (class "Default")
      (node (ref "C3") (pin "1") (pinfunction "1_1") (pintype "passive"))
      (node (ref "L2") (pin "1") (pinfunction "1_1") (pintype "passive"))
      (node (ref "LPC1769") (pin "10") (pinfunction "VDDA_10") (pintype "power_in"))
      (node (ref "LPC1769") (pin "12") (pinfunction "VREFP_12") (pintype "power_in"))
    )
    (net (code "214") (name "Net-(LPC1769-XTAL1)") (class "Default")
      (node (ref "C12") (pin "1") (pinfunction "1_1") (pintype "passive"))
      (node (ref "LPC1769") (pin "22") (pinfunction "XTAL1_22") (pintype "bidirectional"))
      (node (ref "U$3") (pin "XTAL2") (pinfunction "2_XTAL2") (pintype "passive"))
    )
    (net (code "215") (name "Net-(LPC1769-XTAL2)") (class "Default")
      (node (ref "C13") (pin "1") (pinfunction "1_1") (pintype "passive"))
      (node (ref "LPC1769") (pin "23") (pinfunction "XTAL2_23") (pintype "bidirectional"))
      (node (ref "U$3") (pin "XTAL1") (pinfunction "1_XTAL1") (pintype "passive"))
    )
    (net (code "216") (name "Net-(MS1-Pad1)") (class "Default")
      (node (ref "MS1") (pin "1") (pinfunction "1_1") (pintype "passive"))
      (node (ref "MS2") (pin "1") (pinfunction "1_1") (pintype "passive"))
      (node (ref "MS3") (pin "1") (pinfunction "1_1") (pintype "passive"))
      (node (ref "R14") (pin "1") (pinfunction "1_1") (pintype "passive"))
    )
    (net (code "217") (name "Net-(MS4-Pad1)") (class "Default")
      (node (ref "MS4") (pin "1") (pinfunction "1_1") (pintype "passive"))
      (node (ref "MS5") (pin "1") (pinfunction "1_1") (pintype "passive"))
      (node (ref "MS6") (pin "1") (pinfunction "1_1") (pintype "passive"))
      (node (ref "R31") (pin "1") (pinfunction "1_1") (pintype "passive"))
    )
    (net (code "218") (name "Net-(MS7-Pad1)") (class "Default")
      (node (ref "MS7") (pin "1") (pinfunction "1_1") (pintype "passive"))
      (node (ref "MS8") (pin "1") (pinfunction "1_1") (pintype "passive"))
      (node (ref "MS9") (pin "1") (pinfunction "1_1") (pintype "passive"))
      (node (ref "R39") (pin "1") (pinfunction "1_1") (pintype "passive"))
    )
    (net (code "219") (name "Net-(MS10-Pad1)") (class "Default")
      (node (ref "MS10") (pin "1") (pinfunction "1_1") (pintype "passive"))
      (node (ref "MS11") (pin "1") (pinfunction "1_1") (pintype "passive"))
      (node (ref "MS12") (pin "1") (pinfunction "1_1") (pintype "passive"))
      (node (ref "R47") (pin "1") (pinfunction "1_1") (pintype "passive"))
    )
    (net (code "220") (name "Net-(MS13-Pad1)") (class "Default")
      (node (ref "MS13") (pin "1") (pinfunction "1_1") (pintype "passive"))
      (node (ref "MS14") (pin "1") (pinfunction "1_1") (pintype "passive"))
      (node (ref "MS15") (pin "1") (pinfunction "1_1") (pintype "passive"))
      (node (ref "R55") (pin "1") (pinfunction "1_1") (pintype "passive"))
    )
    (net (code "221") (name "Net-(Q1-PadB)") (class "Default")
      (node (ref "Q1") (pin "B") (pinfunction "B_B") (pintype "passive"))
      (node (ref "R3") (pin "2") (pinfunction "2_2") (pintype "passive"))
    )
    (net (code "222") (name "Net-(Q1-PadC)") (class "Default")
      (node (ref "Q1") (pin "C") (pinfunction "C_C") (pintype "passive"))
      (node (ref "R73") (pin "2") (pinfunction "2_2") (pintype "passive"))
    )
    (net (code "223") (name "Net-(R68-Pad1)") (class "Default")
      (node (ref "R68") (pin "1") (pinfunction "1_1") (pintype "passive"))
      (node (ref "RJ1") (pin "Y_GND") (pinfunction "Y_GND_Y_GND") (pintype "bidirectional"))
    )
    (net (code "224") (name "Net-(R69-Pad1)") (class "Default")
      (node (ref "R69") (pin "1") (pinfunction "1_1") (pintype "passive"))
      (node (ref "RJ1") (pin "G_GND") (pinfunction "G_GND_G_GND") (pintype "bidirectional"))
    )
    (net (code "225") (name "Net-(R74-Pad2)") (class "Default")
      (node (ref "R74") (pin "2") (pinfunction "2_2") (pintype "passive"))
      (node (ref "RX") (pin "A") (pinfunction "A_A") (pintype "passive"))
    )
    (net (code "226") (name "Net-(R75-Pad2)") (class "Default")
      (node (ref "R75") (pin "2") (pinfunction "2_2") (pintype "passive"))
      (node (ref "TX") (pin "A") (pinfunction "A_A") (pintype "passive"))
    )
    (net (code "227") (name "Net-(U$8A-1)") (class "Default")
      (node (ref "C65") (pin "1") (pinfunction "1_1") (pintype "passive"))
      (node (ref "R62") (pin "2") (pinfunction "2_2") (pintype "passive"))
      (node (ref "U$8") (pin "XTAL1") (pinfunction "1_XTAL1") (pintype "passive"))
      (node (ref "U3") (pin "4") (pinfunction "XTAL2_4") (pintype "bidirectional"))
    )
    (net (code "228") (name "Net-(U$8A-2)") (class "Default")
      (node (ref "C64") (pin "1") (pinfunction "1_1") (pintype "passive"))
      (node (ref "R62") (pin "1") (pinfunction "1_1") (pintype "passive"))
      (node (ref "U$8") (pin "XTAL2") (pinfunction "2_XTAL2") (pintype "passive"))
      (node (ref "U3") (pin "5") (pinfunction "XTAL1_5") (pintype "bidirectional"))
    )
    (net (code "229") (name "Net-(U3-CRS_DV)") (class "Default")
      (node (ref "R61") (pin "1") (pinfunction "1_1") (pintype "passive"))
      (node (ref "U3") (pin "11") (pinfunction "CRS_DV_11") (pintype "bidirectional"))
    )
    (net (code "230") (name "Net-(U3-NINT{slash}REFCLKO)") (class "Default")
      (node (ref "U3") (pin "14") (pinfunction "NINT/REFCLKO_14") (pintype "bidirectional"))
      (node (ref "U4") (pin "2") (pinfunction "A_2") (pintype "bidirectional"))
    )
    (net (code "231") (name "Net-(U3-RBIAS)") (class "Default")
      (node (ref "R63") (pin "1") (pinfunction "1_1") (pintype "passive"))
      (node (ref "U3") (pin "24") (pinfunction "RBIAS_24") (pintype "bidirectional"))
    )
    (net (code "232") (name "Net-(U3-RX+)") (class "Default")
      (node (ref "C68") (pin "1") (pinfunction "1_1") (pintype "passive"))
      (node (ref "R66") (pin "2") (pinfunction "2_2") (pintype "passive"))
      (node (ref "RJ1") (pin "RD+") (pinfunction "RD+_RD+") (pintype "bidirectional"))
      (node (ref "U3") (pin "23") (pinfunction "RX+_23") (pintype "bidirectional"))
    )
    (net (code "233") (name "Net-(U3-RX-)") (class "Default")
      (node (ref "C69") (pin "1") (pinfunction "1_1") (pintype "passive"))
      (node (ref "R67") (pin "2") (pinfunction "2_2") (pintype "passive"))
      (node (ref "RJ1") (pin "RD-") (pinfunction "RD-_RD-") (pintype "bidirectional"))
      (node (ref "U3") (pin "22") (pinfunction "RX-_22") (pintype "bidirectional"))
    )
    (net (code "234") (name "Net-(U3-RXD0)") (class "Default")
      (node (ref "R59") (pin "1") (pinfunction "1_1") (pintype "passive"))
      (node (ref "U3") (pin "8") (pinfunction "RXD0_8") (pintype "bidirectional"))
    )
    (net (code "235") (name "Net-(U3-RXD1)") (class "Default")
      (node (ref "R60") (pin "1") (pinfunction "1_1") (pintype "passive"))
      (node (ref "U3") (pin "7") (pinfunction "RXD1_7") (pintype "bidirectional"))
    )
    (net (code "236") (name "Net-(U3-TX+)") (class "Default")
      (node (ref "C66") (pin "1") (pinfunction "1_1") (pintype "passive"))
      (node (ref "R64") (pin "2") (pinfunction "2_2") (pintype "passive"))
      (node (ref "RJ1") (pin "TD+") (pinfunction "TD+_TD+") (pintype "bidirectional"))
      (node (ref "U3") (pin "21") (pinfunction "TX+_21") (pintype "bidirectional"))
    )
    (net (code "237") (name "Net-(U3-TX-)") (class "Default")
      (node (ref "C67") (pin "1") (pinfunction "1_1") (pintype "passive"))
      (node (ref "R65") (pin "2") (pinfunction "2_2") (pintype "passive"))
      (node (ref "RJ1") (pin "TD-") (pinfunction "TD-_TD-") (pintype "bidirectional"))
      (node (ref "U3") (pin "20") (pinfunction "TX-_20") (pintype "bidirectional"))
    )
    (net (code "238") (name "Net-(V_HEATB-KL)") (class "Default")
      (node (ref "F4") (pin "P$1") (pinfunction "P$1_P$1") (pintype "bidirectional"))
      (node (ref "V_HEAT") (pin "2") (pinfunction "KL_2") (pintype "passive"))
    )
    (net (code "239") (name "Net-(V_MOTB-KL)") (class "Default")
      (node (ref "F3") (pin "1") (pinfunction "1_1") (pintype "passive"))
      (node (ref "V_MOT") (pin "2") (pinfunction "KL_2") (pintype "passive"))
    )
    (net (code "240") (name "Net-(X_MAXB-S)") (class "Default")
      (node (ref "END_STOP_V") (pin "2") (pinfunction "2_2") (pintype "passive"))
      (node (ref "X_MAX") (pin "2") (pinfunction "S_2") (pintype "passive"))
      (node (ref "X_MIN") (pin "2") (pinfunction "S_2") (pintype "passive"))
      (node (ref "Y_MAX") (pin "2") (pinfunction "S_2") (pintype "passive"))
      (node (ref "Y_MIN") (pin "2") (pinfunction "S_2") (pintype "passive"))
      (node (ref "Z_MAX") (pin "2") (pinfunction "S_2") (pintype "passive"))
      (node (ref "Z_MIN") (pin "2") (pinfunction "S_2") (pintype "passive"))
    )
    (net (code "241") (name "VHEAT") (class "Default")
      (node (ref "C74") (pin "+") (pinfunction "+_+") (pintype "passive"))
      (node (ref "D2") (pin "C") (pinfunction "C_C") (pintype "passive"))
      (node (ref "E0") (pin "1") (pinfunction "KL_1") (pintype "passive"))
      (node (ref "E1") (pin "1") (pinfunction "KL_1") (pintype "passive"))
      (node (ref "F4") (pin "P$2") (pinfunction "P$2_P$2") (pintype "bidirectional"))
      (node (ref "FAN1") (pin "2") (pinfunction "S_2") (pintype "passive"))
      (node (ref "FAN2") (pin "2") (pinfunction "S_2") (pintype "passive"))
      (node (ref "FAN3") (pin "2") (pinfunction "S_2") (pintype "passive"))
      (node (ref "HB") (pin "1") (pinfunction "KL_1") (pintype "passive"))
      (node (ref "R17") (pin "1") (pinfunction "1_1") (pintype "passive"))
      (node (ref "R19") (pin "1") (pinfunction "1_1") (pintype "passive"))
      (node (ref "R21") (pin "1") (pinfunction "1_1") (pintype "passive"))
      (node (ref "R94") (pin "1") (pinfunction "1_1") (pintype "passive"))
      (node (ref "R95") (pin "1") (pinfunction "1_1") (pintype "passive"))
      (node (ref "R96") (pin "1") (pinfunction "1_1") (pintype "passive"))
    )
    (net (code "242") (name "VMOT") (class "Default")
      (node (ref "C20") (pin "2") (pinfunction "2_2") (pintype "passive"))
      (node (ref "C21") (pin "2") (pinfunction "2_2") (pintype "passive"))
      (node (ref "C22") (pin "2") (pinfunction "2_2") (pintype "passive"))
      (node (ref "C23") (pin "+") (pinfunction "+_+") (pintype "passive"))
      (node (ref "C30") (pin "2") (pinfunction "2_2") (pintype "passive"))
      (node (ref "C31") (pin "2") (pinfunction "2_2") (pintype "passive"))
      (node (ref "C32") (pin "2") (pinfunction "2_2") (pintype "passive"))
      (node (ref "C33") (pin "+") (pinfunction "+_+") (pintype "passive"))
      (node (ref "C37") (pin "2") (pinfunction "2_2") (pintype "passive"))
      (node (ref "C38") (pin "2") (pinfunction "2_2") (pintype "passive"))
      (node (ref "C39") (pin "2") (pinfunction "2_2") (pintype "passive"))
      (node (ref "C40") (pin "+") (pinfunction "+_+") (pintype "passive"))
      (node (ref "C44") (pin "2") (pinfunction "2_2") (pintype "passive"))
      (node (ref "C45") (pin "2") (pinfunction "2_2") (pintype "passive"))
      (node (ref "C46") (pin "2") (pinfunction "2_2") (pintype "passive"))
      (node (ref "C47") (pin "+") (pinfunction "+_+") (pintype "passive"))
      (node (ref "C51") (pin "2") (pinfunction "2_2") (pintype "passive"))
      (node (ref "C52") (pin "2") (pinfunction "2_2") (pintype "passive"))
      (node (ref "C53") (pin "2") (pinfunction "2_2") (pintype "passive"))
      (node (ref "C54") (pin "+") (pinfunction "+_+") (pintype "passive"))
      (node (ref "C75") (pin "1") (pinfunction "1_1") (pintype "passive"))
      (node (ref "C78") (pin "+") (pinfunction "+_+") (pintype "passive"))
      (node (ref "D3") (pin "C") (pinfunction "C_C") (pintype "passive"))
      (node (ref "F3") (pin "2") (pinfunction "2_2") (pintype "passive"))
      (node (ref "IC2") (pin "22") (pinfunction "VBB1_22") (pintype "power_in"))
      (node (ref "IC2") (pin "28") (pinfunction "VBB2_28") (pintype "power_in"))
      (node (ref "IC3") (pin "22") (pinfunction "VBB1_22") (pintype "power_in"))
      (node (ref "IC3") (pin "28") (pinfunction "VBB2_28") (pintype "power_in"))
      (node (ref "IC4") (pin "22") (pinfunction "VBB1_22") (pintype "power_in"))
      (node (ref "IC4") (pin "28") (pinfunction "VBB2_28") (pintype "power_in"))
      (node (ref "IC5") (pin "22") (pinfunction "VBB1_22") (pintype "power_in"))
      (node (ref "IC5") (pin "28") (pinfunction "VBB2_28") (pintype "power_in"))
      (node (ref "IC6") (pin "22") (pinfunction "VBB1_22") (pintype "power_in"))
      (node (ref "IC6") (pin "28") (pinfunction "VBB2_28") (pintype "power_in"))
      (node (ref "IC8") (pin "7") (pinfunction "VIN_7") (pintype "input"))
      (node (ref "R90") (pin "2") (pinfunction "2_2") (pintype "passive"))
    )
    (net (code "243") (name "unconnected-(AD5206-A5-Pad12)") (class "Default")
      (node (ref "AD5206") (pin "12") (pinfunction "A5_12") (pintype "bidirectional"))
    )
    (net (code "244") (name "unconnected-(AD5206-B5-Pad10)") (class "Default")
      (node (ref "AD5206") (pin "10") (pinfunction "B5_10") (pintype "bidirectional"))
    )
    (net (code "245") (name "unconnected-(AD5206-W5-Pad11)") (class "Default")
      (node (ref "AD5206") (pin "11") (pinfunction "W5_11") (pintype "bidirectional"))
    )
    (net (code "246") (name "unconnected-(IC2-NC-Pad7)") (class "Default")
      (node (ref "IC2") (pin "7") (pinfunction "NC_7") (pintype "no_connect"))
    )
    (net (code "247") (name "unconnected-(IC2-NC-Pad20)") (class "Default")
      (node (ref "IC2") (pin "20") (pinfunction "NC_20") (pintype "no_connect"))
    )
    (net (code "248") (name "unconnected-(IC2-NC-Pad25)") (class "Default")
      (node (ref "IC2") (pin "25") (pinfunction "NC_25") (pintype "no_connect"))
    )
    (net (code "249") (name "unconnected-(IC3-NC-Pad7)") (class "Default")
      (node (ref "IC3") (pin "7") (pinfunction "NC_7") (pintype "no_connect"))
    )
    (net (code "250") (name "unconnected-(IC3-NC-Pad20)") (class "Default")
      (node (ref "IC3") (pin "20") (pinfunction "NC_20") (pintype "no_connect"))
    )
    (net (code "251") (name "unconnected-(IC3-NC-Pad25)") (class "Default")
      (node (ref "IC3") (pin "25") (pinfunction "NC_25") (pintype "no_connect"))
    )
    (net (code "252") (name "unconnected-(IC4-NC-Pad7)") (class "Default")
      (node (ref "IC4") (pin "7") (pinfunction "NC_7") (pintype "no_connect"))
    )
    (net (code "253") (name "unconnected-(IC4-NC-Pad20)") (class "Default")
      (node (ref "IC4") (pin "20") (pinfunction "NC_20") (pintype "no_connect"))
    )
    (net (code "254") (name "unconnected-(IC4-NC-Pad25)") (class "Default")
      (node (ref "IC4") (pin "25") (pinfunction "NC_25") (pintype "no_connect"))
    )
    (net (code "255") (name "unconnected-(IC5-NC-Pad7)") (class "Default")
      (node (ref "IC5") (pin "7") (pinfunction "NC_7") (pintype "no_connect"))
    )
    (net (code "256") (name "unconnected-(IC5-NC-Pad20)") (class "Default")
      (node (ref "IC5") (pin "20") (pinfunction "NC_20") (pintype "no_connect"))
    )
    (net (code "257") (name "unconnected-(IC5-NC-Pad25)") (class "Default")
      (node (ref "IC5") (pin "25") (pinfunction "NC_25") (pintype "no_connect"))
    )
    (net (code "258") (name "unconnected-(IC6-NC-Pad7)") (class "Default")
      (node (ref "IC6") (pin "7") (pinfunction "NC_7") (pintype "no_connect"))
    )
    (net (code "259") (name "unconnected-(IC6-NC-Pad20)") (class "Default")
      (node (ref "IC6") (pin "20") (pinfunction "NC_20") (pintype "no_connect"))
    )
    (net (code "260") (name "unconnected-(IC6-NC-Pad25)") (class "Default")
      (node (ref "IC6") (pin "25") (pinfunction "NC_25") (pintype "no_connect"))
    )
    (net (code "261") (name "unconnected-(IC7-CTS-Pad11)") (class "Default")
      (node (ref "IC7") (pin "11") (pinfunction "CTS_11") (pintype "input"))
    )
    (net (code "262") (name "unconnected-(IC7-DCD-Pad10)") (class "Default")
      (node (ref "IC7") (pin "10") (pinfunction "DCD_10") (pintype "input"))
    )
    (net (code "263") (name "unconnected-(IC7-DSR-Pad9)") (class "Default")
      (node (ref "IC7") (pin "9") (pinfunction "DSR_9") (pintype "input"))
    )
    (net (code "264") (name "unconnected-(IC7-DTR-Pad2)") (class "Default")
      (node (ref "IC7") (pin "2") (pinfunction "DTR_2") (pintype "output"))
    )
    (net (code "265") (name "unconnected-(IC7-OSCI-Pad27)") (class "Default")
      (node (ref "IC7") (pin "27") (pinfunction "OSCI_27") (pintype "input"))
    )
    (net (code "266") (name "unconnected-(IC7-OSCO-Pad28)") (class "Default")
      (node (ref "IC7") (pin "28") (pinfunction "OSCO_28") (pintype "output"))
    )
    (net (code "267") (name "unconnected-(IC7-PWREN-Pad14)") (class "Default")
      (node (ref "IC7") (pin "14") (pinfunction "PWREN_14") (pintype "input"))
    )
    (net (code "268") (name "unconnected-(IC7-RESET-Pad19)") (class "Default")
      (node (ref "IC7") (pin "19") (pinfunction "RESET_19") (pintype "input"))
    )
    (net (code "269") (name "unconnected-(IC7-RI-Pad6)") (class "Default")
      (node (ref "IC7") (pin "6") (pinfunction "RI_6") (pintype "input"))
    )
    (net (code "270") (name "unconnected-(IC7-RTS-Pad3)") (class "Default")
      (node (ref "IC7") (pin "3") (pinfunction "RTS_3") (pintype "output"))
    )
    (net (code "271") (name "unconnected-(IC7-SLEEP-Pad12)") (class "Default")
      (node (ref "IC7") (pin "12") (pinfunction "SLEEP_12") (pintype "input"))
    )
    (net (code "272") (name "unconnected-(IC7-TXDEN-Pad13)") (class "Default")
      (node (ref "IC7") (pin "13") (pinfunction "TXDEN_13") (pintype "input"))
    )
    (net (code "273") (name "unconnected-(IC8-~{ON{slash}OFF}-Pad5)") (class "Default")
      (node (ref "IC8") (pin "5") (pinfunction "~{ON/OFF}_5") (pintype "passive"))
    )
    (net (code "274") (name "unconnected-(LPC1769-N.C.-Pad13)") (class "Default")
      (node (ref "LPC1769") (pin "13") (pinfunction "N.C._13") (pintype "no_connect"))
    )
    (net (code "275") (name "unconnected-(LPC1769-P1[21]{slash}MCABORT{slash}PWM1[3]{slash}SSEL0-Pad35)") (class "Default")
      (node (ref "LPC1769") (pin "35") (pinfunction "P1[21]/MCABORT/PWM1[3]/SSEL0_35") (pintype "bidirectional"))
    )
    (net (code "276") (name "unconnected-(LPC1769-RTCX1-Pad16)") (class "Default")
      (node (ref "LPC1769") (pin "16") (pinfunction "RTCX1_16") (pintype "bidirectional"))
    )
    (net (code "277") (name "unconnected-(LPC1769-RTCX2-Pad18)") (class "Default")
      (node (ref "LPC1769") (pin "18") (pinfunction "RTCX2_18") (pintype "bidirectional"))
    )
    (net (code "278") (name "unconnected-(U$7-PadID)") (class "Default")
      (node (ref "U$7") (pin "ID") (pinfunction "ID_ID") (pintype "bidirectional"))
    )
    (net (code "279") (name "unconnected-(U2-NC-Pad1)") (class "Default")
      (node (ref "U2") (pin "1") (pinfunction "NC_1") (pintype "bidirectional"))
    )
    (net (code "280") (name "unconnected-(U2-RSV-Pad8)") (class "Default")
      (node (ref "U2") (pin "8") (pinfunction "RSV_8") (pintype "bidirectional"))
    )
    (net (code "281") (name "unconnected-(U2-SHIELD-PadCD1)") (class "Default")
      (node (ref "U2") (pin "CD1") (pinfunction "SHIELD_CD1") (pintype "bidirectional"))
    )
    (net (code "282") (name "unconnected-(U2-SHIELD-PadCD2)") (class "Default")
      (node (ref "U2") (pin "CD2") (pinfunction "SHIELD_CD2") (pintype "bidirectional"))
    )
    (net (code "283") (name "unconnected-(U4-NC-Pad1)") (class "Default")
      (node (ref "U4") (pin "1") (pinfunction "NC_1") (pintype "no_connect"))
    )
  )
)
